# SM3320-BATT-EV.net
KiCad netlist of a schematic drawn in Altium Designer
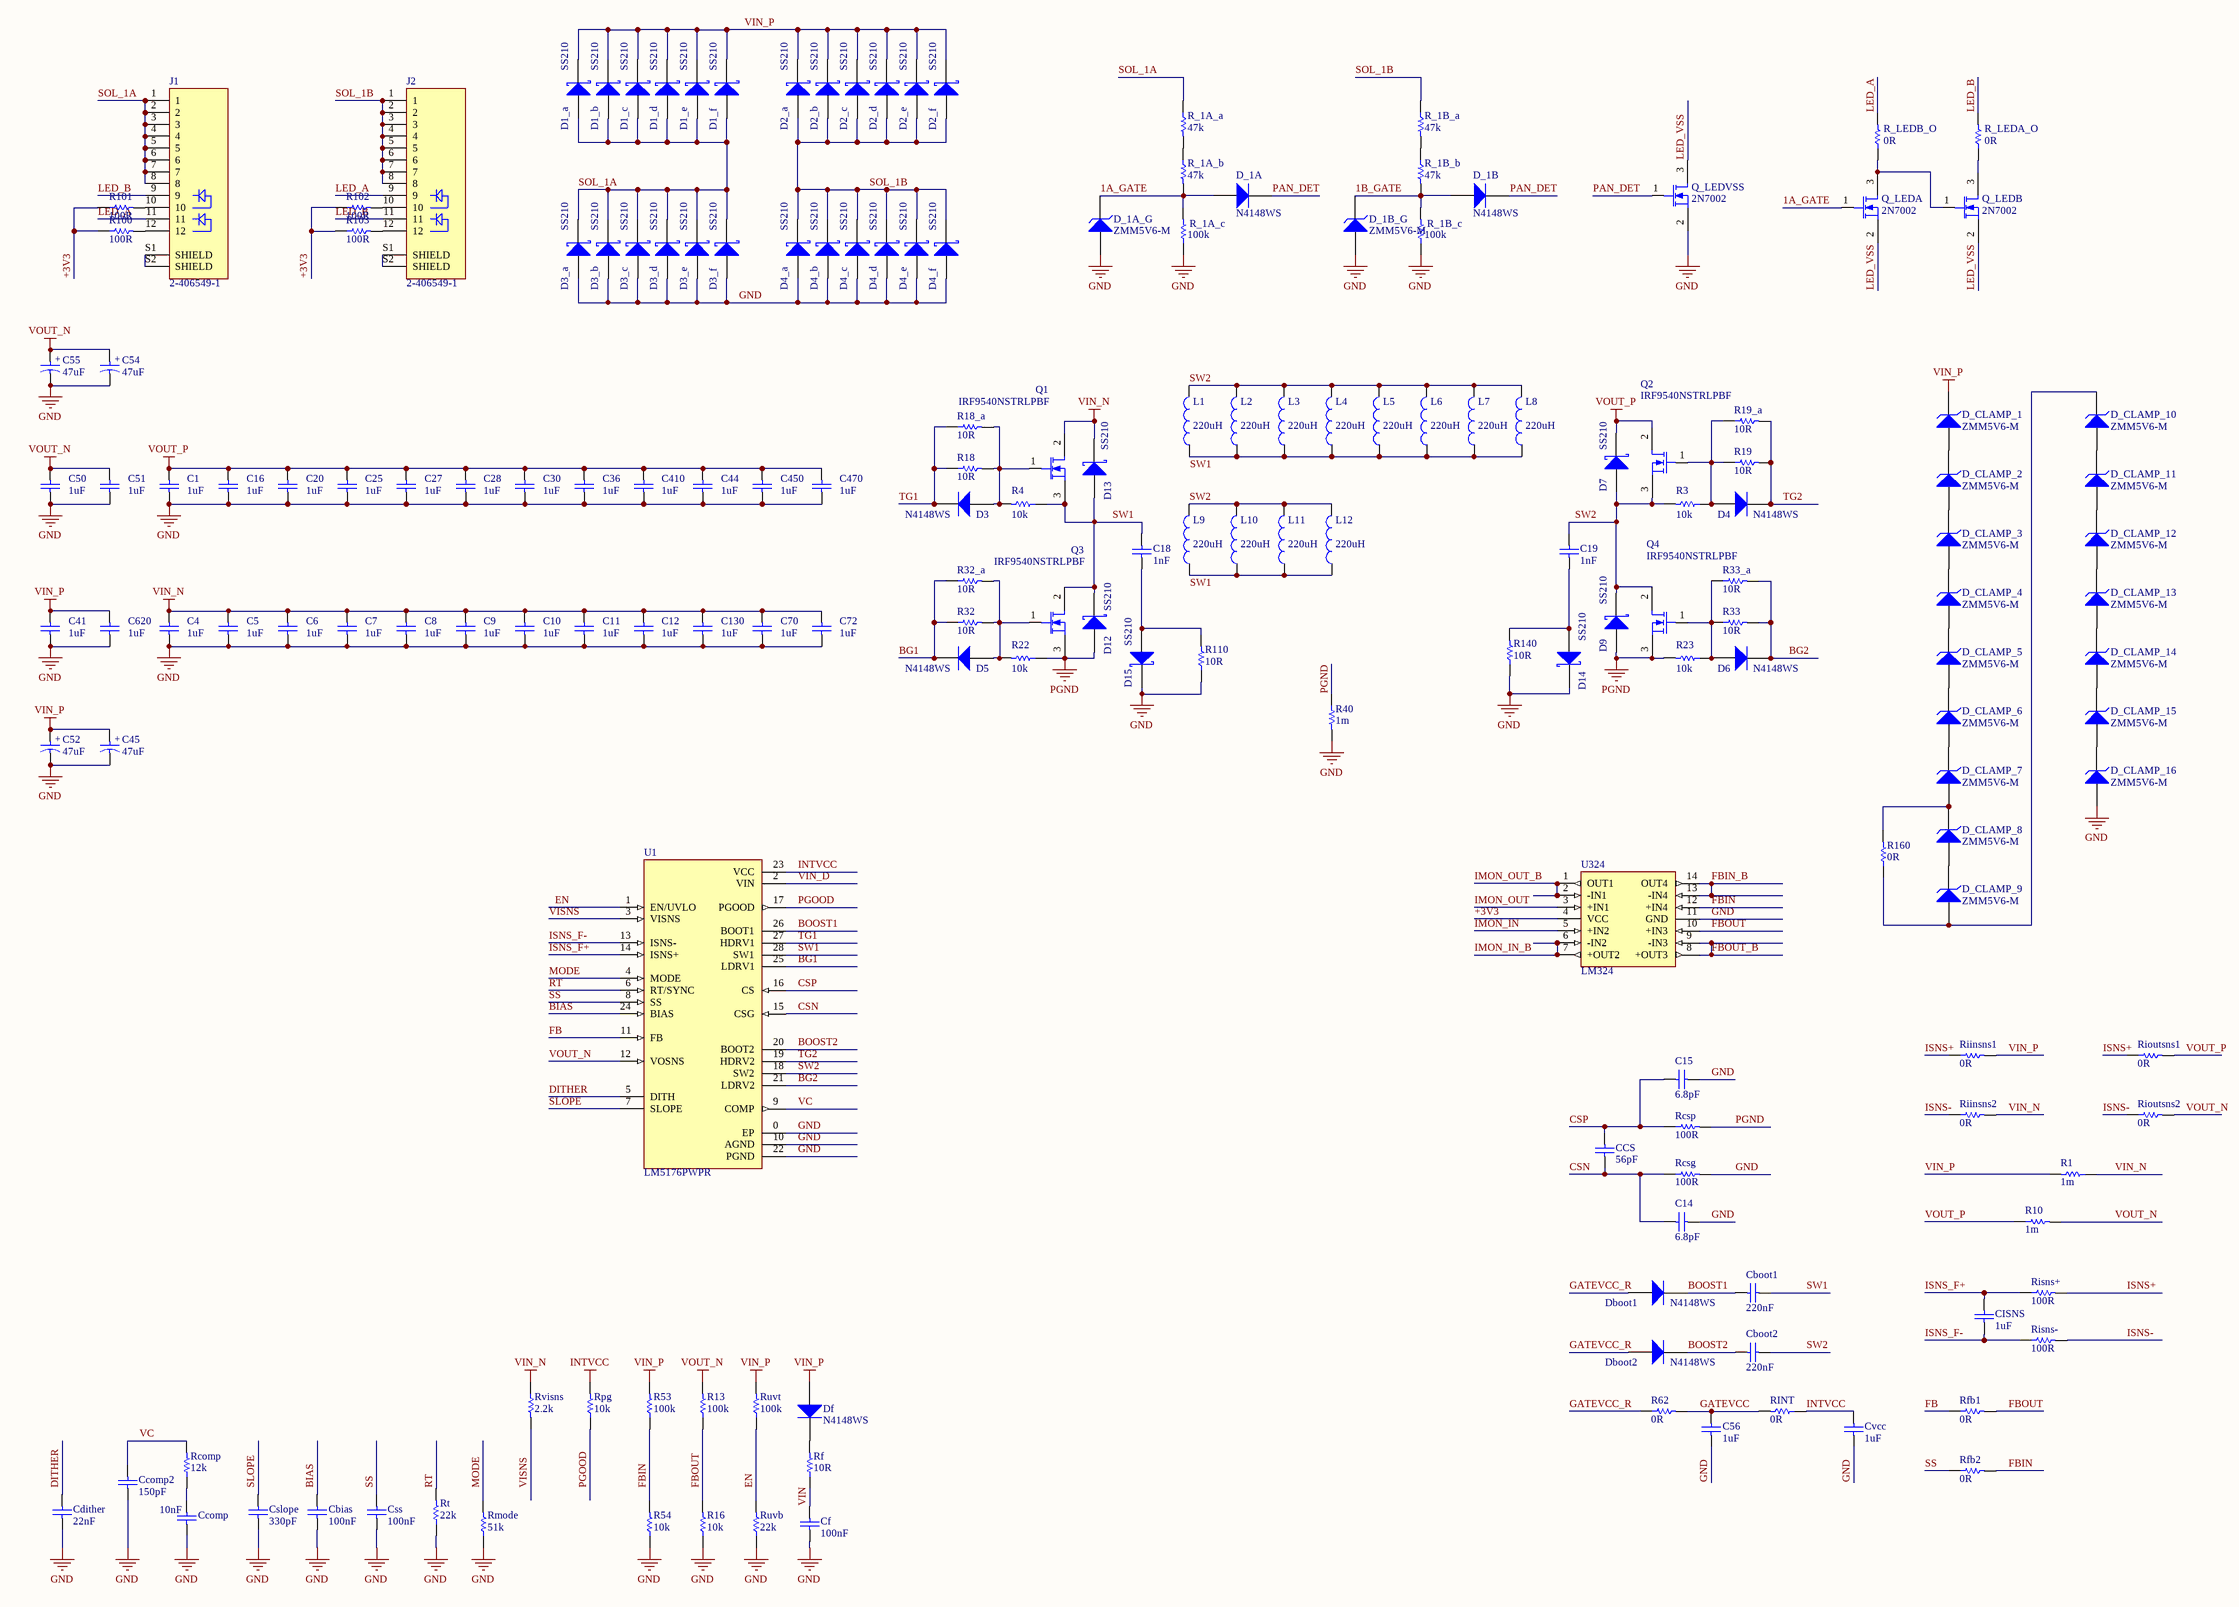
[diagram p0: SM3320-BATT-EV.SchDoc]

(export (version "E")
  (design (tool "Eeschema 10.0.6"))
  (components
    (comp (ref "C1")
      (value "1uF")
      (footprint "C_1206")
      (description "C - CAPACITOR - MLCC - 1uF - 100V - 1206 - X7R")
      (fields (field (name "LCSC PART #") "C91151") (field (name "Comment") "1206B105K101NT"))
      (libsource (lib "JLC_PCB") (part "1206B105K101NT"))
    )
    (comp (ref "C4")
      (value "1uF")
      (footprint "C_1206")
      (description "C - CAPACITOR - MLCC - 1uF - 100V - 1206 - X7R")
      (fields (field (name "LCSC PART #") "C91151") (field (name "Comment") "1206B105K101NT"))
      (libsource (lib "JLC_PCB") (part "1206B105K101NT"))
    )
    (comp (ref "C5")
      (value "1uF")
      (footprint "C_1206")
      (description "C - CAPACITOR - MLCC - 1uF - 100V - 1206 - X7R")
      (fields (field (name "LCSC PART #") "C91151") (field (name "Comment") "1206B105K101NT"))
      (libsource (lib "JLC_PCB") (part "1206B105K101NT"))
    )
    (comp (ref "C6")
      (value "1uF")
      (footprint "C_1206")
      (description "C - CAPACITOR - MLCC - 1uF - 100V - 1206 - X7R")
      (fields (field (name "LCSC PART #") "C91151") (field (name "Comment") "1206B105K101NT"))
      (libsource (lib "JLC_PCB") (part "1206B105K101NT"))
    )
    (comp (ref "C7")
      (value "1uF")
      (footprint "C_1206")
      (description "C - CAPACITOR - MLCC - 1uF - 100V - 1206 - X7R")
      (fields (field (name "LCSC PART #") "C91151") (field (name "Comment") "1206B105K101NT"))
      (libsource (lib "JLC_PCB") (part "1206B105K101NT"))
    )
    (comp (ref "C8")
      (value "1uF")
      (footprint "C_1206")
      (description "C - CAPACITOR - MLCC - 1uF - 100V - 1206 - X7R")
      (fields (field (name "LCSC PART #") "C91151") (field (name "Comment") "1206B105K101NT"))
      (libsource (lib "JLC_PCB") (part "1206B105K101NT"))
    )
    (comp (ref "C9")
      (value "1uF")
      (footprint "C_1206")
      (description "C - CAPACITOR - MLCC - 1uF - 100V - 1206 - X7R")
      (fields (field (name "LCSC PART #") "C91151") (field (name "Comment") "1206B105K101NT"))
      (libsource (lib "JLC_PCB") (part "1206B105K101NT"))
    )
    (comp (ref "C10")
      (value "1uF")
      (footprint "C_1206")
      (description "C - CAPACITOR - MLCC - 1uF - 100V - 1206 - X7R")
      (fields (field (name "LCSC PART #") "C91151") (field (name "Comment") "1206B105K101NT"))
      (libsource (lib "JLC_PCB") (part "1206B105K101NT"))
    )
    (comp (ref "C11")
      (value "1uF")
      (footprint "C_1206")
      (description "C - CAPACITOR - MLCC - 1uF - 100V - 1206 - X7R")
      (fields (field (name "LCSC PART #") "C91151") (field (name "Comment") "1206B105K101NT"))
      (libsource (lib "JLC_PCB") (part "1206B105K101NT"))
    )
    (comp (ref "C12")
      (value "1uF")
      (footprint "C_1206")
      (description "C - CAPACITOR - MLCC - 1uF - 100V - 1206 - X7R")
      (fields (field (name "LCSC PART #") "C91151") (field (name "Comment") "1206B105K101NT"))
      (libsource (lib "JLC_PCB") (part "1206B105K101NT"))
    )
    (comp (ref "C14")
      (value "6.8pF")
      (footprint "C_0402")
      (description "C - CAPACITOR - MLCC - 6.8pF - 50V - 0402")
      (fields (field (name "LCSC PART #") "C1576") (field (name "Comment") "0402CG6R8C500NT"))
      (libsource (lib "JLC_PCB") (part "0402CG6R8C500NT"))
    )
    (comp (ref "C15")
      (value "6.8pF")
      (footprint "C_0402")
      (description "C - CAPACITOR - MLCC - 6.8pF - 50V - 0402")
      (fields (field (name "LCSC PART #") "C1576") (field (name "Comment") "0402CG6R8C500NT"))
      (libsource (lib "JLC_PCB") (part "0402CG6R8C500NT"))
    )
    (comp (ref "C16")
      (value "1uF")
      (footprint "C_1206")
      (description "C - CAPACITOR - MLCC - 1uF - 100V - 1206 - X7R")
      (fields (field (name "LCSC PART #") "C91151") (field (name "Comment") "1206B105K101NT"))
      (libsource (lib "JLC_PCB") (part "1206B105K101NT"))
    )
    (comp (ref "C18")
      (value "1nF")
      (footprint "C_1206")
      (description "C - CAPACITOR - MLCC - 1nF - 2000V - 1206 - X7R")
      (fields (field (name "LCSC PART #") "C9196") (field (name "Comment") "1206B102K202NT"))
      (libsource (lib "JLC_PCB") (part "1206B102K202NT"))
    )
    (comp (ref "C19")
      (value "1nF")
      (footprint "C_1206")
      (description "C - CAPACITOR - MLCC - 1nF - 2000V - 1206 - X7R")
      (fields (field (name "LCSC PART #") "C9196") (field (name "Comment") "1206B102K202NT"))
      (libsource (lib "JLC_PCB") (part "1206B102K202NT"))
    )
    (comp (ref "C20")
      (value "1uF")
      (footprint "C_1206")
      (description "C - CAPACITOR - MLCC - 1uF - 100V - 1206 - X7R")
      (fields (field (name "LCSC PART #") "C91151") (field (name "Comment") "1206B105K101NT"))
      (libsource (lib "JLC_PCB") (part "1206B105K101NT"))
    )
    (comp (ref "C25")
      (value "1uF")
      (footprint "C_1206")
      (description "C - CAPACITOR - MLCC - 1uF - 100V - 1206 - X7R")
      (fields (field (name "LCSC PART #") "C91151") (field (name "Comment") "1206B105K101NT"))
      (libsource (lib "JLC_PCB") (part "1206B105K101NT"))
    )
    (comp (ref "C27")
      (value "1uF")
      (footprint "C_1206")
      (description "C - CAPACITOR - MLCC - 1uF - 100V - 1206 - X7R")
      (fields (field (name "LCSC PART #") "C91151") (field (name "Comment") "1206B105K101NT"))
      (libsource (lib "JLC_PCB") (part "1206B105K101NT"))
    )
    (comp (ref "C28")
      (value "1uF")
      (footprint "C_1206")
      (description "C - CAPACITOR - MLCC - 1uF - 100V - 1206 - X7R")
      (fields (field (name "LCSC PART #") "C91151") (field (name "Comment") "1206B105K101NT"))
      (libsource (lib "JLC_PCB") (part "1206B105K101NT"))
    )
    (comp (ref "C30")
      (value "1uF")
      (footprint "C_1206")
      (description "C - CAPACITOR - MLCC - 1uF - 100V - 1206 - X7R")
      (fields (field (name "LCSC PART #") "C91151") (field (name "Comment") "1206B105K101NT"))
      (libsource (lib "JLC_PCB") (part "1206B105K101NT"))
    )
    (comp (ref "C36")
      (value "1uF")
      (footprint "C_1206")
      (description "C - CAPACITOR - MLCC - 1uF - 100V - 1206 - X7R")
      (fields (field (name "LCSC PART #") "C91151") (field (name "Comment") "1206B105K101NT"))
      (libsource (lib "JLC_PCB") (part "1206B105K101NT"))
    )
    (comp (ref "C41")
      (value "1uF")
      (footprint "C_1206")
      (description "C - CAPACITOR - MLCC - 1uF - 100V - 1206 - X7R")
      (fields (field (name "LCSC PART #") "C91151") (field (name "Comment") "1206B105K101NT"))
      (libsource (lib "JLC_PCB") (part "1206B105K101NT"))
    )
    (comp (ref "C44")
      (value "1uF")
      (footprint "C_1206")
      (description "C - CAPACITOR - MLCC - 1uF - 100V - 1206 - X7R")
      (fields (field (name "LCSC PART #") "C91151") (field (name "Comment") "1206B105K101NT"))
      (libsource (lib "JLC_PCB") (part "1206B105K101NT"))
    )
    (comp (ref "C45")
      (value "47uF")
      (footprint "C_CAN_1010")
      (description "C - CAPACITOR - ELECTROLYTIC - 47uF - 100V")
      (fields (field (name "LCSC PART #") "C164068") (field (name "Comment") "VZH470M2ATR-1010"))
      (libsource (lib "JLC_PCB") (part "VZH470M2ATR-1010"))
    )
    (comp (ref "C50")
      (value "1uF")
      (footprint "C_1206")
      (description "C - CAPACITOR - MLCC - 1uF - 100V - 1206 - X7R")
      (fields (field (name "LCSC PART #") "C91151") (field (name "Comment") "1206B105K101NT"))
      (libsource (lib "JLC_PCB") (part "1206B105K101NT"))
    )
    (comp (ref "C51")
      (value "1uF")
      (footprint "C_1206")
      (description "C - CAPACITOR - MLCC - 1uF - 100V - 1206 - X7R")
      (fields (field (name "LCSC PART #") "C91151") (field (name "Comment") "1206B105K101NT"))
      (libsource (lib "JLC_PCB") (part "1206B105K101NT"))
    )
    (comp (ref "C52")
      (value "47uF")
      (footprint "C_CAN_1010")
      (description "C - CAPACITOR - ELECTROLYTIC - 47uF - 100V")
      (fields (field (name "LCSC PART #") "C164068") (field (name "Comment") "VZH470M2ATR-1010"))
      (libsource (lib "JLC_PCB") (part "VZH470M2ATR-1010"))
    )
    (comp (ref "C54")
      (value "47uF")
      (footprint "C_CAN_1010")
      (description "C - CAPACITOR - ELECTROLYTIC - 47uF - 100V")
      (fields (field (name "LCSC PART #") "C164068") (field (name "Comment") "VZH470M2ATR-1010"))
      (libsource (lib "JLC_PCB") (part "VZH470M2ATR-1010"))
    )
    (comp (ref "C55")
      (value "47uF")
      (footprint "C_CAN_1010")
      (description "C - CAPACITOR - ELECTROLYTIC - 47uF - 100V")
      (fields (field (name "LCSC PART #") "C164068") (field (name "Comment") "VZH470M2ATR-1010"))
      (libsource (lib "JLC_PCB") (part "VZH470M2ATR-1010"))
    )
    (comp (ref "C56")
      (value "1uF")
      (footprint "C_0402")
      (description "C - CAPACITOR - MLCC - 1uF - 25V - 0402")
      (fields (field (name "LCSC PART #") "C52923") (field (name "Comment") "CL05A105KA5NQNC"))
      (libsource (lib "JLC_PCB") (part "CL05A105KA5NQNC"))
    )
    (comp (ref "C70")
      (value "1uF")
      (footprint "C_1206")
      (description "C - CAPACITOR - MLCC - 1uF - 100V - 1206 - X7R")
      (fields (field (name "LCSC PART #") "C91151") (field (name "Comment") "1206B105K101NT"))
      (libsource (lib "JLC_PCB") (part "1206B105K101NT"))
    )
    (comp (ref "C72")
      (value "1uF")
      (footprint "C_1206")
      (description "C - CAPACITOR - MLCC - 1uF - 100V - 1206 - X7R")
      (fields (field (name "LCSC PART #") "C91151") (field (name "Comment") "1206B105K101NT"))
      (libsource (lib "JLC_PCB") (part "1206B105K101NT"))
    )
    (comp (ref "C130")
      (value "1uF")
      (footprint "C_1206")
      (description "C - CAPACITOR - MLCC - 1uF - 100V - 1206 - X7R")
      (fields (field (name "LCSC PART #") "C91151") (field (name "Comment") "1206B105K101NT"))
      (libsource (lib "JLC_PCB") (part "1206B105K101NT"))
    )
    (comp (ref "C410")
      (value "1uF")
      (footprint "C_1206")
      (description "C - CAPACITOR - MLCC - 1uF - 100V - 1206 - X7R")
      (fields (field (name "LCSC PART #") "C91151") (field (name "Comment") "1206B105K101NT"))
      (libsource (lib "JLC_PCB") (part "1206B105K101NT"))
    )
    (comp (ref "C450")
      (value "1uF")
      (footprint "C_1206")
      (description "C - CAPACITOR - MLCC - 1uF - 100V - 1206 - X7R")
      (fields (field (name "LCSC PART #") "C91151") (field (name "Comment") "1206B105K101NT"))
      (libsource (lib "JLC_PCB") (part "1206B105K101NT"))
    )
    (comp (ref "C470")
      (value "1uF")
      (footprint "C_1206")
      (description "C - CAPACITOR - MLCC - 1uF - 100V - 1206 - X7R")
      (fields (field (name "LCSC PART #") "C91151") (field (name "Comment") "1206B105K101NT"))
      (libsource (lib "JLC_PCB") (part "1206B105K101NT"))
    )
    (comp (ref "C620")
      (value "1uF")
      (footprint "C_1206")
      (description "C - CAPACITOR - MLCC - 1uF - 100V - 1206 - X7R")
      (fields (field (name "LCSC PART #") "C91151") (field (name "Comment") "1206B105K101NT"))
      (libsource (lib "JLC_PCB") (part "1206B105K101NT"))
    )
    (comp (ref "Cbias")
      (value "100nF")
      (footprint "C_0603")
      (description "C - CAPACITOR - MLCC - 100nF - 50V - 0603")
      (fields (field (name "LCSC PART #") "C14663") (field (name "Comment") "CC0603KRX7R9BB104"))
      (libsource (lib "JLC_PCB") (part "CC0603KRX7R9BB104"))
    )
    (comp (ref "Cboot1")
      (value "220nF")
      (footprint "C_0402")
      (description "C - CAPACITOR - MLCC - 220nF - 16V - 0402")
      (fields (field (name "LCSC PART #") "C16772") (field (name "Comment") "CL05B224KO5NNNC"))
      (libsource (lib "JLC_PCB") (part "CL05B224KO5NNNC"))
    )
    (comp (ref "Cboot2")
      (value "220nF")
      (footprint "C_0402")
      (description "C - CAPACITOR - MLCC - 220nF - 16V - 0402")
      (fields (field (name "LCSC PART #") "C16772") (field (name "Comment") "CL05B224KO5NNNC"))
      (libsource (lib "JLC_PCB") (part "CL05B224KO5NNNC"))
    )
    (comp (ref "Ccomp")
      (value "10nF")
      (footprint "C_0402")
      (description "C - CAPACITOR - MLCC - 10nF - 50V - 0402")
      (fields (field (name "LCSC PART #") "C15195") (field (name "Comment") "CL05B103KB5NNNC"))
      (libsource (lib "JLC_PCB") (part "CL05B103KB5NNNC"))
    )
    (comp (ref "Ccomp2")
      (value "150pF")
      (footprint "C_0402")
      (description "C - CAPACITOR - MLCC - 150pF - 50V - 0402")
      (fields (field (name "LCSC PART #") "C1527") (field (name "Comment") "0402B151K500NT"))
      (libsource (lib "JLC_PCB") (part "0402B151K500NT"))
    )
    (comp (ref "CCS")
      (value "56pF")
      (footprint "C_0402")
      (description "C - CAPACITOR - MLCC - 56pF - 50V -  0402")
      (fields (field (name "LCSC PART #") "C1572") (field (name "Comment") "0402CG560J500NT"))
      (libsource (lib "JLC_PCB") (part "0402CG560J500NT"))
    )
    (comp (ref "Cdither")
      (value "22nF")
      (footprint "C_0402")
      (description "C - CAPACITOR - MLCC - 22nF - 50V - 0402")
      (fields (field (name "LCSC PART #") "C1532") (field (name "Comment") "0402B223K500NT"))
      (libsource (lib "JLC_PCB") (part "0402B223K500NT"))
    )
    (comp (ref "Cf")
      (value "100nF")
      (footprint "C_0603")
      (description "C - CAPACITOR - MLCC - 100nF - 50V - 0603")
      (fields (field (name "LCSC PART #") "C14663") (field (name "Comment") "CC0603KRX7R9BB104"))
      (libsource (lib "JLC_PCB") (part "CC0603KRX7R9BB104"))
    )
    (comp (ref "CISNS")
      (value "1uF")
      (footprint "C_0402")
      (description "C - CAPACITOR - MLCC - 1uF - 25V - 0402")
      (fields (field (name "LCSC PART #") "C52923") (field (name "Comment") "CL05A105KA5NQNC"))
      (libsource (lib "JLC_PCB") (part "CL05A105KA5NQNC"))
    )
    (comp (ref "Cslope")
      (value "330pF")
      (footprint "C_0603")
      (description "C - CAPACITOR - MLCC - 330pF - 50V - 0603")
      (fields (field (name "LCSC PART #") "C1664") (field (name "Comment") "CL10C331JB8NNNC"))
      (libsource (lib "JLC_PCB") (part "CL10C331JB8NNNC"))
    )
    (comp (ref "Css")
      (value "100nF")
      (footprint "C_0402")
      (description "C - CAPACITOR - MLCC - 100nF - 16V - 0402")
      (fields (field (name "LCSC PART #") "C1525") (field (name "Comment") "CL05B104KO5NNNC"))
      (libsource (lib "JLC_PCB") (part "CL05B104KO5NNNC"))
    )
    (comp (ref "Cvcc")
      (value "1uF")
      (footprint "C_0402")
      (description "C - CAPACITOR - MLCC - 1uF - 25V - 0402")
      (fields (field (name "LCSC PART #") "C52923") (field (name "Comment") "CL05A105KA5NQNC"))
      (libsource (lib "JLC_PCB") (part "CL05A105KA5NQNC"))
    )
    (comp (ref "D1_a")
      (value "SS210")
      (footprint "DO-214AC")
      (description "D - DIODE - SCHOTTKY - 100V - 2A")
      (fields (field (name "LCSC PART #") "C14996"))
      (libsource (lib "JLC_PCB") (part "SS210"))
    )
    (comp (ref "D1_b")
      (value "SS210")
      (footprint "DO-214AC")
      (description "D - DIODE - SCHOTTKY - 100V - 2A")
      (fields (field (name "LCSC PART #") "C14996"))
      (libsource (lib "JLC_PCB") (part "SS210"))
    )
    (comp (ref "D1_c")
      (value "SS210")
      (footprint "DO-214AC")
      (description "D - DIODE - SCHOTTKY - 100V - 2A")
      (fields (field (name "LCSC PART #") "C14996"))
      (libsource (lib "JLC_PCB") (part "SS210"))
    )
    (comp (ref "D1_d")
      (value "SS210")
      (footprint "DO-214AC")
      (description "D - DIODE - SCHOTTKY - 100V - 2A")
      (fields (field (name "LCSC PART #") "C14996"))
      (libsource (lib "JLC_PCB") (part "SS210"))
    )
    (comp (ref "D1_e")
      (value "SS210")
      (footprint "DO-214AC")
      (description "D - DIODE - SCHOTTKY - 100V - 2A")
      (fields (field (name "LCSC PART #") "C14996"))
      (libsource (lib "JLC_PCB") (part "SS210"))
    )
    (comp (ref "D1_f")
      (value "SS210")
      (footprint "DO-214AC")
      (description "D - DIODE - SCHOTTKY - 100V - 2A")
      (fields (field (name "LCSC PART #") "C14996"))
      (libsource (lib "JLC_PCB") (part "SS210"))
    )
    (comp (ref "D2_a")
      (value "SS210")
      (footprint "DO-214AC")
      (description "D - DIODE - SCHOTTKY - 100V - 2A")
      (fields (field (name "LCSC PART #") "C14996"))
      (libsource (lib "JLC_PCB") (part "SS210"))
    )
    (comp (ref "D2_b")
      (value "SS210")
      (footprint "DO-214AC")
      (description "D - DIODE - SCHOTTKY - 100V - 2A")
      (fields (field (name "LCSC PART #") "C14996"))
      (libsource (lib "JLC_PCB") (part "SS210"))
    )
    (comp (ref "D2_c")
      (value "SS210")
      (footprint "DO-214AC")
      (description "D - DIODE - SCHOTTKY - 100V - 2A")
      (fields (field (name "LCSC PART #") "C14996"))
      (libsource (lib "JLC_PCB") (part "SS210"))
    )
    (comp (ref "D2_d")
      (value "SS210")
      (footprint "DO-214AC")
      (description "D - DIODE - SCHOTTKY - 100V - 2A")
      (fields (field (name "LCSC PART #") "C14996"))
      (libsource (lib "JLC_PCB") (part "SS210"))
    )
    (comp (ref "D2_e")
      (value "SS210")
      (footprint "DO-214AC")
      (description "D - DIODE - SCHOTTKY - 100V - 2A")
      (fields (field (name "LCSC PART #") "C14996"))
      (libsource (lib "JLC_PCB") (part "SS210"))
    )
    (comp (ref "D2_f")
      (value "SS210")
      (footprint "DO-214AC")
      (description "D - DIODE - SCHOTTKY - 100V - 2A")
      (fields (field (name "LCSC PART #") "C14996"))
      (libsource (lib "JLC_PCB") (part "SS210"))
    )
    (comp (ref "D3")
      (value "N4148WS")
      (footprint "SOD-323")
      (description "D - DIODE - FAST TRR - 100V - 150mA - 4ns")
      (fields (field (name "LCSC PART #") "C2128"))
      (libsource (lib "JLC_PCB") (part "N4148WS"))
    )
    (comp (ref "D3_a")
      (value "SS210")
      (footprint "DO-214AC")
      (description "D - DIODE - SCHOTTKY - 100V - 2A")
      (fields (field (name "LCSC PART #") "C14996"))
      (libsource (lib "JLC_PCB") (part "SS210"))
    )
    (comp (ref "D3_b")
      (value "SS210")
      (footprint "DO-214AC")
      (description "D - DIODE - SCHOTTKY - 100V - 2A")
      (fields (field (name "LCSC PART #") "C14996"))
      (libsource (lib "JLC_PCB") (part "SS210"))
    )
    (comp (ref "D3_c")
      (value "SS210")
      (footprint "DO-214AC")
      (description "D - DIODE - SCHOTTKY - 100V - 2A")
      (fields (field (name "LCSC PART #") "C14996"))
      (libsource (lib "JLC_PCB") (part "SS210"))
    )
    (comp (ref "D3_d")
      (value "SS210")
      (footprint "DO-214AC")
      (description "D - DIODE - SCHOTTKY - 100V - 2A")
      (fields (field (name "LCSC PART #") "C14996"))
      (libsource (lib "JLC_PCB") (part "SS210"))
    )
    (comp (ref "D3_e")
      (value "SS210")
      (footprint "DO-214AC")
      (description "D - DIODE - SCHOTTKY - 100V - 2A")
      (fields (field (name "LCSC PART #") "C14996"))
      (libsource (lib "JLC_PCB") (part "SS210"))
    )
    (comp (ref "D3_f")
      (value "SS210")
      (footprint "DO-214AC")
      (description "D - DIODE - SCHOTTKY - 100V - 2A")
      (fields (field (name "LCSC PART #") "C14996"))
      (libsource (lib "JLC_PCB") (part "SS210"))
    )
    (comp (ref "D4")
      (value "N4148WS")
      (footprint "SOD-323")
      (description "D - DIODE - FAST TRR - 100V - 150mA - 4ns")
      (fields (field (name "LCSC PART #") "C2128"))
      (libsource (lib "JLC_PCB") (part "N4148WS"))
    )
    (comp (ref "D4_a")
      (value "SS210")
      (footprint "DO-214AC")
      (description "D - DIODE - SCHOTTKY - 100V - 2A")
      (fields (field (name "LCSC PART #") "C14996"))
      (libsource (lib "JLC_PCB") (part "SS210"))
    )
    (comp (ref "D4_b")
      (value "SS210")
      (footprint "DO-214AC")
      (description "D - DIODE - SCHOTTKY - 100V - 2A")
      (fields (field (name "LCSC PART #") "C14996"))
      (libsource (lib "JLC_PCB") (part "SS210"))
    )
    (comp (ref "D4_c")
      (value "SS210")
      (footprint "DO-214AC")
      (description "D - DIODE - SCHOTTKY - 100V - 2A")
      (fields (field (name "LCSC PART #") "C14996"))
      (libsource (lib "JLC_PCB") (part "SS210"))
    )
    (comp (ref "D4_d")
      (value "SS210")
      (footprint "DO-214AC")
      (description "D - DIODE - SCHOTTKY - 100V - 2A")
      (fields (field (name "LCSC PART #") "C14996"))
      (libsource (lib "JLC_PCB") (part "SS210"))
    )
    (comp (ref "D4_e")
      (value "SS210")
      (footprint "DO-214AC")
      (description "D - DIODE - SCHOTTKY - 100V - 2A")
      (fields (field (name "LCSC PART #") "C14996"))
      (libsource (lib "JLC_PCB") (part "SS210"))
    )
    (comp (ref "D4_f")
      (value "SS210")
      (footprint "DO-214AC")
      (description "D - DIODE - SCHOTTKY - 100V - 2A")
      (fields (field (name "LCSC PART #") "C14996"))
      (libsource (lib "JLC_PCB") (part "SS210"))
    )
    (comp (ref "D5")
      (value "N4148WS")
      (footprint "SOD-323")
      (description "D - DIODE - FAST TRR - 100V - 150mA - 4ns")
      (fields (field (name "LCSC PART #") "C2128"))
      (libsource (lib "JLC_PCB") (part "N4148WS"))
    )
    (comp (ref "D6")
      (value "N4148WS")
      (footprint "SOD-323")
      (description "D - DIODE - FAST TRR - 100V - 150mA - 4ns")
      (fields (field (name "LCSC PART #") "C2128"))
      (libsource (lib "JLC_PCB") (part "N4148WS"))
    )
    (comp (ref "D7")
      (value "SS210")
      (footprint "DO-214AC")
      (description "D - DIODE - SCHOTTKY - 100V - 2A")
      (fields (field (name "LCSC PART #") "C14996"))
      (libsource (lib "JLC_PCB") (part "SS210"))
    )
    (comp (ref "D9")
      (value "SS210")
      (footprint "DO-214AC")
      (description "D - DIODE - SCHOTTKY - 100V - 2A")
      (fields (field (name "LCSC PART #") "C14996"))
      (libsource (lib "JLC_PCB") (part "SS210"))
    )
    (comp (ref "D12")
      (value "SS210")
      (footprint "DO-214AC")
      (description "D - DIODE - SCHOTTKY - 100V - 2A")
      (fields (field (name "LCSC PART #") "C14996"))
      (libsource (lib "JLC_PCB") (part "SS210"))
    )
    (comp (ref "D13")
      (value "SS210")
      (footprint "DO-214AC")
      (description "D - DIODE - SCHOTTKY - 100V - 2A")
      (fields (field (name "LCSC PART #") "C14996"))
      (libsource (lib "JLC_PCB") (part "SS210"))
    )
    (comp (ref "D14")
      (value "SS210")
      (footprint "DO-214AC")
      (description "D - DIODE - SCHOTTKY - 100V - 2A")
      (fields (field (name "LCSC PART #") "C14996"))
      (libsource (lib "JLC_PCB") (part "SS210"))
    )
    (comp (ref "D15")
      (value "SS210")
      (footprint "DO-214AC")
      (description "D - DIODE - SCHOTTKY - 100V - 2A")
      (fields (field (name "LCSC PART #") "C14996"))
      (libsource (lib "JLC_PCB") (part "SS210"))
    )
    (comp (ref "Dboot1")
      (value "N4148WS")
      (footprint "SOD-323")
      (description "D - DIODE - FAST TRR - 100V - 150mA - 4ns")
      (fields (field (name "LCSC PART #") "C2128"))
      (libsource (lib "JLC_PCB") (part "N4148WS"))
    )
    (comp (ref "Dboot2")
      (value "N4148WS")
      (footprint "SOD-323")
      (description "D - DIODE - FAST TRR - 100V - 150mA - 4ns")
      (fields (field (name "LCSC PART #") "C2128"))
      (libsource (lib "JLC_PCB") (part "N4148WS"))
    )
    (comp (ref "Df")
      (value "N4148WS")
      (footprint "SOD-323")
      (description "D - DIODE - FAST TRR - 100V - 150mA - 4ns")
      (fields (field (name "LCSC PART #") "C2128"))
      (libsource (lib "JLC_PCB") (part "N4148WS"))
    )
    (comp (ref "D_1A")
      (value "N4148WS")
      (footprint "SOD-323")
      (description "D - DIODE - FAST TRR - 100V - 150mA - 4ns")
      (fields (field (name "LCSC PART #") "C2128"))
      (libsource (lib "JLC_PCB") (part "N4148WS"))
    )
    (comp (ref "D_1A_G")
      (value "ZMM5V6-M")
      (footprint "DO-213AA")
      (description "D - DIODE - ZENER - 5.6V - 500mW")
      (fields (field (name "LCSC PART #") "C8062"))
      (libsource (lib "JLC_PCB") (part "ZMM5V6-M"))
    )
    (comp (ref "D_1B")
      (value "N4148WS")
      (footprint "SOD-323")
      (description "D - DIODE - FAST TRR - 100V - 150mA - 4ns")
      (fields (field (name "LCSC PART #") "C2128"))
      (libsource (lib "JLC_PCB") (part "N4148WS"))
    )
    (comp (ref "D_1B_G")
      (value "ZMM5V6-M")
      (footprint "DO-213AA")
      (description "D - DIODE - ZENER - 5.6V - 500mW")
      (fields (field (name "LCSC PART #") "C8062"))
      (libsource (lib "JLC_PCB") (part "ZMM5V6-M"))
    )
    (comp (ref "D_CLAMP_1")
      (value "ZMM5V6-M")
      (footprint "DO-213AA")
      (description "D - DIODE - ZENER - 5.6V - 500mW")
      (fields (field (name "LCSC PART #") "C8062"))
      (libsource (lib "JLC_PCB") (part "ZMM5V6-M"))
    )
    (comp (ref "D_CLAMP_2")
      (value "ZMM5V6-M")
      (footprint "DO-213AA")
      (description "D - DIODE - ZENER - 5.6V - 500mW")
      (fields (field (name "LCSC PART #") "C8062"))
      (libsource (lib "JLC_PCB") (part "ZMM5V6-M"))
    )
    (comp (ref "D_CLAMP_3")
      (value "ZMM5V6-M")
      (footprint "DO-213AA")
      (description "D - DIODE - ZENER - 5.6V - 500mW")
      (fields (field (name "LCSC PART #") "C8062"))
      (libsource (lib "JLC_PCB") (part "ZMM5V6-M"))
    )
    (comp (ref "D_CLAMP_4")
      (value "ZMM5V6-M")
      (footprint "DO-213AA")
      (description "D - DIODE - ZENER - 5.6V - 500mW")
      (fields (field (name "LCSC PART #") "C8062"))
      (libsource (lib "JLC_PCB") (part "ZMM5V6-M"))
    )
    (comp (ref "D_CLAMP_5")
      (value "ZMM5V6-M")
      (footprint "DO-213AA")
      (description "D - DIODE - ZENER - 5.6V - 500mW")
      (fields (field (name "LCSC PART #") "C8062"))
      (libsource (lib "JLC_PCB") (part "ZMM5V6-M"))
    )
    (comp (ref "D_CLAMP_6")
      (value "ZMM5V6-M")
      (footprint "DO-213AA")
      (description "D - DIODE - ZENER - 5.6V - 500mW")
      (fields (field (name "LCSC PART #") "C8062"))
      (libsource (lib "JLC_PCB") (part "ZMM5V6-M"))
    )
    (comp (ref "D_CLAMP_7")
      (value "ZMM5V6-M")
      (footprint "DO-213AA")
      (description "D - DIODE - ZENER - 5.6V - 500mW")
      (fields (field (name "LCSC PART #") "C8062"))
      (libsource (lib "JLC_PCB") (part "ZMM5V6-M"))
    )
    (comp (ref "D_CLAMP_8")
      (value "ZMM5V6-M")
      (footprint "DO-213AA")
      (description "D - DIODE - ZENER - 5.6V - 500mW")
      (fields (field (name "LCSC PART #") "C8062"))
      (libsource (lib "JLC_PCB") (part "ZMM5V6-M"))
    )
    (comp (ref "D_CLAMP_9")
      (value "ZMM5V6-M")
      (footprint "DO-213AA")
      (description "D - DIODE - ZENER - 5.6V - 500mW")
      (fields (field (name "LCSC PART #") "C8062"))
      (libsource (lib "JLC_PCB") (part "ZMM5V6-M"))
    )
    (comp (ref "D_CLAMP_10")
      (value "ZMM5V6-M")
      (footprint "DO-213AA")
      (description "D - DIODE - ZENER - 5.6V - 500mW")
      (fields (field (name "LCSC PART #") "C8062"))
      (libsource (lib "JLC_PCB") (part "ZMM5V6-M"))
    )
    (comp (ref "D_CLAMP_11")
      (value "ZMM5V6-M")
      (footprint "DO-213AA")
      (description "D - DIODE - ZENER - 5.6V - 500mW")
      (fields (field (name "LCSC PART #") "C8062"))
      (libsource (lib "JLC_PCB") (part "ZMM5V6-M"))
    )
    (comp (ref "D_CLAMP_12")
      (value "ZMM5V6-M")
      (footprint "DO-213AA")
      (description "D - DIODE - ZENER - 5.6V - 500mW")
      (fields (field (name "LCSC PART #") "C8062"))
      (libsource (lib "JLC_PCB") (part "ZMM5V6-M"))
    )
    (comp (ref "D_CLAMP_13")
      (value "ZMM5V6-M")
      (footprint "DO-213AA")
      (description "D - DIODE - ZENER - 5.6V - 500mW")
      (fields (field (name "LCSC PART #") "C8062"))
      (libsource (lib "JLC_PCB") (part "ZMM5V6-M"))
    )
    (comp (ref "D_CLAMP_14")
      (value "ZMM5V6-M")
      (footprint "DO-213AA")
      (description "D - DIODE - ZENER - 5.6V - 500mW")
      (fields (field (name "LCSC PART #") "C8062"))
      (libsource (lib "JLC_PCB") (part "ZMM5V6-M"))
    )
    (comp (ref "D_CLAMP_15")
      (value "ZMM5V6-M")
      (footprint "DO-213AA")
      (description "D - DIODE - ZENER - 5.6V - 500mW")
      (fields (field (name "LCSC PART #") "C8062"))
      (libsource (lib "JLC_PCB") (part "ZMM5V6-M"))
    )
    (comp (ref "D_CLAMP_16")
      (value "ZMM5V6-M")
      (footprint "DO-213AA")
      (description "D - DIODE - ZENER - 5.6V - 500mW")
      (fields (field (name "LCSC PART #") "C8062"))
      (libsource (lib "JLC_PCB") (part "ZMM5V6-M"))
    )
    (comp (ref "J1")
      (value "2-406549-1")
      (footprint "TE_2-406549-1")
      (description "J - JACK - ETHERNET - Right - THT")
      (fields (field (name "LCSC PART #") "C125068"))
      (libsource (lib "JLC_PCB") (part "2-406549-1"))
    )
    (comp (ref "J2")
      (value "2-406549-1")
      (footprint "TE_2-406549-1")
      (description "J - JACK - ETHERNET - Right - THT")
      (fields (field (name "LCSC PART #") "C125068"))
      (libsource (lib "JLC_PCB") (part "2-406549-1"))
    )
    (comp (ref "L1")
      (value "220uH")
      (footprint "SRR1260")
      (description "L - INDUCTOR - 220uH - 1.6A - 12.5mm")
      (fields (field (name "LCSC PART #") "C169380") (field (name "Comment") "SWRB1207S-221MT"))
      (libsource (lib "JLC_PCB") (part "SWRB1207S-221MT"))
    )
    (comp (ref "L2")
      (value "220uH")
      (footprint "SRR1260")
      (description "L - INDUCTOR - 220uH - 1.6A - 12.5mm")
      (fields (field (name "LCSC PART #") "C169380") (field (name "Comment") "SWRB1207S-221MT"))
      (libsource (lib "JLC_PCB") (part "SWRB1207S-221MT"))
    )
    (comp (ref "L3")
      (value "220uH")
      (footprint "SRR1260")
      (description "L - INDUCTOR - 220uH - 1.6A - 12.5mm")
      (fields (field (name "LCSC PART #") "C169380") (field (name "Comment") "SWRB1207S-221MT"))
      (libsource (lib "JLC_PCB") (part "SWRB1207S-221MT"))
    )
    (comp (ref "L4")
      (value "220uH")
      (footprint "SRR1260")
      (description "L - INDUCTOR - 220uH - 1.6A - 12.5mm")
      (fields (field (name "LCSC PART #") "C169380") (field (name "Comment") "SWRB1207S-221MT"))
      (libsource (lib "JLC_PCB") (part "SWRB1207S-221MT"))
    )
    (comp (ref "L5")
      (value "220uH")
      (footprint "SRR1260")
      (description "L - INDUCTOR - 220uH - 1.6A - 12.5mm")
      (fields (field (name "LCSC PART #") "C169380") (field (name "Comment") "SWRB1207S-221MT"))
      (libsource (lib "JLC_PCB") (part "SWRB1207S-221MT"))
    )
    (comp (ref "L6")
      (value "220uH")
      (footprint "SRR1260")
      (description "L - INDUCTOR - 220uH - 1.6A - 12.5mm")
      (fields (field (name "LCSC PART #") "C169380") (field (name "Comment") "SWRB1207S-221MT"))
      (libsource (lib "JLC_PCB") (part "SWRB1207S-221MT"))
    )
    (comp (ref "L7")
      (value "220uH")
      (footprint "SRR1260")
      (description "L - INDUCTOR - 220uH - 1.6A - 12.5mm")
      (fields (field (name "LCSC PART #") "C169380") (field (name "Comment") "SWRB1207S-221MT"))
      (libsource (lib "JLC_PCB") (part "SWRB1207S-221MT"))
    )
    (comp (ref "L8")
      (value "220uH")
      (footprint "SRR1260")
      (description "L - INDUCTOR - 220uH - 1.6A - 12.5mm")
      (fields (field (name "LCSC PART #") "C169380") (field (name "Comment") "SWRB1207S-221MT"))
      (libsource (lib "JLC_PCB") (part "SWRB1207S-221MT"))
    )
    (comp (ref "L9")
      (value "220uH")
      (footprint "SRR1260")
      (description "L - INDUCTOR - 220uH - 1.6A - 12.5mm")
      (fields (field (name "LCSC PART #") "C169380") (field (name "Comment") "SWRB1207S-221MT"))
      (libsource (lib "JLC_PCB") (part "SWRB1207S-221MT"))
    )
    (comp (ref "L10")
      (value "220uH")
      (footprint "SRR1260")
      (description "L - INDUCTOR - 220uH - 1.6A - 12.5mm")
      (fields (field (name "LCSC PART #") "C169380") (field (name "Comment") "SWRB1207S-221MT"))
      (libsource (lib "JLC_PCB") (part "SWRB1207S-221MT"))
    )
    (comp (ref "L11")
      (value "220uH")
      (footprint "SRR1260")
      (description "L - INDUCTOR - 220uH - 1.6A - 12.5mm")
      (fields (field (name "LCSC PART #") "C169380") (field (name "Comment") "SWRB1207S-221MT"))
      (libsource (lib "JLC_PCB") (part "SWRB1207S-221MT"))
    )
    (comp (ref "L12")
      (value "220uH")
      (footprint "SRR1260")
      (description "L - INDUCTOR - 220uH - 1.6A - 12.5mm")
      (fields (field (name "LCSC PART #") "C169380") (field (name "Comment") "SWRB1207S-221MT"))
      (libsource (lib "JLC_PCB") (part "SWRB1207S-221MT"))
    )
    (comp (ref "Q1")
      (value "IRF9540NSTRLPBF")
      (footprint "TO-263-3")
      (description "Q - TRANSISTOR - MOSFET (N) - 250V - 33A - 0.094R")
      (fields (field (name "LCSC PART #") "C33903"))
      (libsource (lib "JLC_PCB") (part "IRF9540NSTRLPBF"))
    )
    (comp (ref "Q2")
      (value "IRF9540NSTRLPBF")
      (footprint "TO-263-3")
      (description "Q - TRANSISTOR - MOSFET (N) - 250V - 33A - 0.094R")
      (fields (field (name "LCSC PART #") "C33903"))
      (libsource (lib "JLC_PCB") (part "IRF9540NSTRLPBF"))
    )
    (comp (ref "Q3")
      (value "IRF9540NSTRLPBF")
      (footprint "TO-263-3")
      (description "Q - TRANSISTOR - MOSFET (N) - 250V - 33A - 0.094R")
      (fields (field (name "LCSC PART #") "C33903"))
      (libsource (lib "JLC_PCB") (part "IRF9540NSTRLPBF"))
    )
    (comp (ref "Q4")
      (value "IRF9540NSTRLPBF")
      (footprint "TO-263-3")
      (description "Q - TRANSISTOR - MOSFET (N) - 250V - 33A - 0.094R")
      (fields (field (name "LCSC PART #") "C33903"))
      (libsource (lib "JLC_PCB") (part "IRF9540NSTRLPBF"))
    )
    (comp (ref "Q_LEDA")
      (value "2N7002")
      (footprint "TO-236AB")
      (description "Q - TRANSISTOR - MOSFET (N) - 60V - 200mW")
      (fields (field (name "LCSC PART #") "C8545"))
      (libsource (lib "JLC_PCB") (part "2N7002"))
    )
    (comp (ref "Q_LEDB")
      (value "2N7002")
      (footprint "TO-236AB")
      (description "Q - TRANSISTOR - MOSFET (N) - 60V - 200mW")
      (fields (field (name "LCSC PART #") "C8545"))
      (libsource (lib "JLC_PCB") (part "2N7002"))
    )
    (comp (ref "Q_LEDVSS")
      (value "2N7002")
      (footprint "TO-236AB")
      (description "Q - TRANSISTOR - MOSFET (N) - 60V - 200mW")
      (fields (field (name "LCSC PART #") "C8545"))
      (libsource (lib "JLC_PCB") (part "2N7002"))
    )
    (comp (ref "R1")
      (value "1m")
      (footprint "R_2512")
      (description "R - RESISTOR - SMD - 0.001R - 1% - 2512 - 2W - 50ppm/k")
      (fields (field (name "LCSC PART #") "C349153") (field (name "POWER") "2W"))
      (libsource (lib "JLC_PCB") (part "EWSL2512F1L00S9"))
    )
    (comp (ref "R3")
      (value "10k")
      (footprint "R_0402")
      (description "R - RESISTOR - SMD - 10k - 1% - 0402")
      (fields (field (name "LCSC PART #") "C25744") (field (name "Comment") "0402WGF1002TCE"))
      (libsource (lib "JLC_PCB") (part "0402WGF1002TCE"))
    )
    (comp (ref "R4")
      (value "10k")
      (footprint "R_0402")
      (description "R - RESISTOR - SMD - 10k - 1% - 0402")
      (fields (field (name "LCSC PART #") "C25744") (field (name "Comment") "0402WGF1002TCE"))
      (libsource (lib "JLC_PCB") (part "0402WGF1002TCE"))
    )
    (comp (ref "R10")
      (value "1m")
      (footprint "R_2512")
      (description "R - RESISTOR - SMD - 0.001R - 1% - 2512 - 2W - 50ppm/k")
      (fields (field (name "LCSC PART #") "C349153") (field (name "POWER") "2W"))
      (libsource (lib "JLC_PCB") (part "EWSL2512F1L00S9"))
    )
    (comp (ref "R13")
      (value "100k")
      (footprint "R_0603")
      (description "R - RESISTOR - SMD - 100k - 1% -  0603")
      (fields (field (name "LCSC PART #") "C22936") (field (name "Comment") "0603WAF100KT5E"))
      (libsource (lib "JLC_PCB") (part "0603WAF100KT5E"))
    )
    (comp (ref "R16")
      (value "10k")
      (footprint "R_0603")
      (description "R - RESISTOR - SMD - 10k - 1% - 0603")
      (fields (field (name "LCSC PART #") "C25804") (field (name "Comment") "0603WAF1002T5E"))
      (libsource (lib "JLC_PCB") (part "0603WAF1002T5E"))
    )
    (comp (ref "R18")
      (value "10R")
      (footprint "R_0402")
      (description "R - RESISTOR - SMD - 10R - 1% - 0402")
      (fields (field (name "LCSC PART #") "C25077") (field (name "Comment") "0402WGF100JTCE"))
      (libsource (lib "JLC_PCB") (part "0402WGF100JTCE"))
    )
    (comp (ref "R18_a")
      (value "10R")
      (footprint "R_0402")
      (description "R - RESISTOR - SMD - 10R - 1% - 0402")
      (fields (field (name "LCSC PART #") "C25077") (field (name "Comment") "0402WGF100JTCE"))
      (libsource (lib "JLC_PCB") (part "0402WGF100JTCE"))
    )
    (comp (ref "R19")
      (value "10R")
      (footprint "R_0402")
      (description "R - RESISTOR - SMD - 10R - 1% - 0402")
      (fields (field (name "LCSC PART #") "C25077") (field (name "Comment") "0402WGF100JTCE"))
      (libsource (lib "JLC_PCB") (part "0402WGF100JTCE"))
    )
    (comp (ref "R19_a")
      (value "10R")
      (footprint "R_0402")
      (description "R - RESISTOR - SMD - 10R - 1% - 0402")
      (fields (field (name "LCSC PART #") "C25077") (field (name "Comment") "0402WGF100JTCE"))
      (libsource (lib "JLC_PCB") (part "0402WGF100JTCE"))
    )
    (comp (ref "R22")
      (value "10k")
      (footprint "R_0402")
      (description "R - RESISTOR - SMD - 10k - 1% - 0402")
      (fields (field (name "LCSC PART #") "C25744") (field (name "Comment") "0402WGF1002TCE"))
      (libsource (lib "JLC_PCB") (part "0402WGF1002TCE"))
    )
    (comp (ref "R23")
      (value "10k")
      (footprint "R_0402")
      (description "R - RESISTOR - SMD - 10k - 1% - 0402")
      (fields (field (name "LCSC PART #") "C25744") (field (name "Comment") "0402WGF1002TCE"))
      (libsource (lib "JLC_PCB") (part "0402WGF1002TCE"))
    )
    (comp (ref "R32")
      (value "10R")
      (footprint "R_0402")
      (description "R - RESISTOR - SMD - 10R - 1% - 0402")
      (fields (field (name "LCSC PART #") "C25077") (field (name "Comment") "0402WGF100JTCE"))
      (libsource (lib "JLC_PCB") (part "0402WGF100JTCE"))
    )
    (comp (ref "R32_a")
      (value "10R")
      (footprint "R_0402")
      (description "R - RESISTOR - SMD - 10R - 1% - 0402")
      (fields (field (name "LCSC PART #") "C25077") (field (name "Comment") "0402WGF100JTCE"))
      (libsource (lib "JLC_PCB") (part "0402WGF100JTCE"))
    )
    (comp (ref "R33")
      (value "10R")
      (footprint "R_0402")
      (description "R - RESISTOR - SMD - 10R - 1% - 0402")
      (fields (field (name "LCSC PART #") "C25077") (field (name "Comment") "0402WGF100JTCE"))
      (libsource (lib "JLC_PCB") (part "0402WGF100JTCE"))
    )
    (comp (ref "R33_a")
      (value "10R")
      (footprint "R_0402")
      (description "R - RESISTOR - SMD - 10R - 1% - 0402")
      (fields (field (name "LCSC PART #") "C25077") (field (name "Comment") "0402WGF100JTCE"))
      (libsource (lib "JLC_PCB") (part "0402WGF100JTCE"))
    )
    (comp (ref "R40")
      (value "1m")
      (footprint "R_2512")
      (description "R - RESISTOR - SMD - 0.001R - 1% - 2512 - 2W - 50ppm/k")
      (fields (field (name "LCSC PART #") "C349153") (field (name "POWER") "2W"))
      (libsource (lib "JLC_PCB") (part "EWSL2512F1L00S9"))
    )
    (comp (ref "R53")
      (value "100k")
      (footprint "R_0603")
      (description "R - RESISTOR - SMD - 100k - 1% -  0603")
      (fields (field (name "LCSC PART #") "C22936") (field (name "Comment") "0603WAF100KT5E"))
      (libsource (lib "JLC_PCB") (part "0603WAF100KT5E"))
    )
    (comp (ref "R54")
      (value "10k")
      (footprint "R_0603")
      (description "R - RESISTOR - SMD - 10k - 1% - 0603")
      (fields (field (name "LCSC PART #") "C25804") (field (name "Comment") "0603WAF1002T5E"))
      (libsource (lib "JLC_PCB") (part "0603WAF1002T5E"))
    )
    (comp (ref "R62")
      (value "0R")
      (footprint "R_0402")
      (description "R - RESISTOR - SMD - 0R - 1% - 0402")
      (fields (field (name "LCSC PART #") "C17168") (field (name "Comment") "0402WGF0000TCE"))
      (libsource (lib "JLC_PCB") (part "0402WGF0000TCE"))
    )
    (comp (ref "R100")
      (value "100R")
      (footprint "R_0402")
      (description "R - RESISTOR - SMD - 100R - 1% - 0402")
      (fields (field (name "LCSC PART #") "C25076") (field (name "Comment") "0402WGF1000TCE"))
      (libsource (lib "JLC_PCB") (part "0402WGF1000TCE"))
    )
    (comp (ref "R101")
      (value "100R")
      (footprint "R_0402")
      (description "R - RESISTOR - SMD - 100R - 1% - 0402")
      (fields (field (name "LCSC PART #") "C25076") (field (name "Comment") "0402WGF1000TCE"))
      (libsource (lib "JLC_PCB") (part "0402WGF1000TCE"))
    )
    (comp (ref "R102")
      (value "100R")
      (footprint "R_0402")
      (description "R - RESISTOR - SMD - 100R - 1% - 0402")
      (fields (field (name "LCSC PART #") "C25076") (field (name "Comment") "0402WGF1000TCE"))
      (libsource (lib "JLC_PCB") (part "0402WGF1000TCE"))
    )
    (comp (ref "R103")
      (value "100R")
      (footprint "R_0402")
      (description "R - RESISTOR - SMD - 100R - 1% - 0402")
      (fields (field (name "LCSC PART #") "C25076") (field (name "Comment") "0402WGF1000TCE"))
      (libsource (lib "JLC_PCB") (part "0402WGF1000TCE"))
    )
    (comp (ref "R110")
      (value "10R")
      (footprint "R_1206")
      (description "R - RESISTOR - SMD - 10R - 1% - 1206")
      (fields (field (name "LCSC PART #") "C17903") (field (name "Comment") "1206W4F100JT5E"))
      (libsource (lib "JLC_PCB") (part "1206W4F100JT5E"))
    )
    (comp (ref "R140")
      (value "10R")
      (footprint "R_1206")
      (description "R - RESISTOR - SMD - 10R - 1% - 1206")
      (fields (field (name "LCSC PART #") "C17903") (field (name "Comment") "1206W4F100JT5E"))
      (libsource (lib "JLC_PCB") (part "1206W4F100JT5E"))
    )
    (comp (ref "R160")
      (value "0R")
      (footprint "R_0402")
      (description "R - RESISTOR - SMD - 0R - 1% - 0402")
      (fields (field (name "LCSC PART #") "C17168") (field (name "Comment") "0402WGF0000TCE"))
      (libsource (lib "JLC_PCB") (part "0402WGF0000TCE"))
    )
    (comp (ref "Rcomp")
      (value "12k")
      (footprint "R_0402")
      (description "R - RESISTOR - SMD - 12k - 1% - 0402")
      (fields (field (name "LCSC PART #") "C25752") (field (name "Comment") "0402WGF1202TCE"))
      (libsource (lib "JLC_PCB") (part "0402WGF1202TCE"))
    )
    (comp (ref "Rcsg")
      (value "100R")
      (footprint "R_0402")
      (description "R - RESISTOR - SMD - 100R - 1% - 0402")
      (fields (field (name "LCSC PART #") "C25076") (field (name "Comment") "0402WGF1000TCE"))
      (libsource (lib "JLC_PCB") (part "0402WGF1000TCE"))
    )
    (comp (ref "Rcsp")
      (value "100R")
      (footprint "R_0402")
      (description "R - RESISTOR - SMD - 100R - 1% - 0402")
      (fields (field (name "LCSC PART #") "C25076") (field (name "Comment") "0402WGF1000TCE"))
      (libsource (lib "JLC_PCB") (part "0402WGF1000TCE"))
    )
    (comp (ref "Rf")
      (value "10R")
      (footprint "R_0402")
      (description "R - RESISTOR - SMD - 10R - 1% - 0402")
      (fields (field (name "LCSC PART #") "C25077") (field (name "Comment") "0402WGF100JTCE"))
      (libsource (lib "JLC_PCB") (part "0402WGF100JTCE"))
    )
    (comp (ref "Rfb1")
      (value "0R")
      (footprint "R_0402")
      (description "R - RESISTOR - SMD - 0R - 1% - 0402")
      (fields (field (name "LCSC PART #") "C17168") (field (name "Comment") "0402WGF0000TCE"))
      (libsource (lib "JLC_PCB") (part "0402WGF0000TCE"))
    )
    (comp (ref "Rfb2")
      (value "0R")
      (footprint "R_0402")
      (description "R - RESISTOR - SMD - 0R - 1% - 0402")
      (fields (field (name "LCSC PART #") "C17168") (field (name "Comment") "0402WGF0000TCE"))
      (libsource (lib "JLC_PCB") (part "0402WGF0000TCE"))
    )
    (comp (ref "Riinsns1")
      (value "0R")
      (footprint "R_0402")
      (description "R - RESISTOR - SMD - 0R - 1% - 0402")
      (fields (field (name "LCSC PART #") "C17168") (field (name "Comment") "0402WGF0000TCE"))
      (libsource (lib "JLC_PCB") (part "0402WGF0000TCE"))
    )
    (comp (ref "Riinsns2")
      (value "0R")
      (footprint "R_0402")
      (description "R - RESISTOR - SMD - 0R - 1% - 0402")
      (fields (field (name "LCSC PART #") "C17168") (field (name "Comment") "0402WGF0000TCE"))
      (libsource (lib "JLC_PCB") (part "0402WGF0000TCE"))
    )
    (comp (ref "RINT")
      (value "0R")
      (footprint "R_0402")
      (description "R - RESISTOR - SMD - 0R - 1% - 0402")
      (fields (field (name "LCSC PART #") "C17168") (field (name "Comment") "0402WGF0000TCE"))
      (libsource (lib "JLC_PCB") (part "0402WGF0000TCE"))
    )
    (comp (ref "Rioutsns1")
      (value "0R")
      (footprint "R_0402")
      (description "R - RESISTOR - SMD - 0R - 1% - 0402")
      (fields (field (name "LCSC PART #") "C17168") (field (name "Comment") "0402WGF0000TCE"))
      (libsource (lib "JLC_PCB") (part "0402WGF0000TCE"))
    )
    (comp (ref "Rioutsns2")
      (value "0R")
      (footprint "R_0402")
      (description "R - RESISTOR - SMD - 0R - 1% - 0402")
      (fields (field (name "LCSC PART #") "C17168") (field (name "Comment") "0402WGF0000TCE"))
      (libsource (lib "JLC_PCB") (part "0402WGF0000TCE"))
    )
    (comp (ref "Risns+")
      (value "100R")
      (footprint "R_0402")
      (description "R - RESISTOR - SMD - 100R - 1% - 0402")
      (fields (field (name "LCSC PART #") "C25076") (field (name "Comment") "0402WGF1000TCE"))
      (libsource (lib "JLC_PCB") (part "0402WGF1000TCE"))
    )
    (comp (ref "Risns-")
      (value "100R")
      (footprint "R_0402")
      (description "R - RESISTOR - SMD - 100R - 1% - 0402")
      (fields (field (name "LCSC PART #") "C25076") (field (name "Comment") "0402WGF1000TCE"))
      (libsource (lib "JLC_PCB") (part "0402WGF1000TCE"))
    )
    (comp (ref "Rmode")
      (value "51k")
      (footprint "R_0402")
      (description "R - RESISTOR - SMD - 51k - 1% - 0402")
      (fields (field (name "LCSC PART #") "C25794") (field (name "Comment") "0402WGF5102TCE"))
      (libsource (lib "JLC_PCB") (part "0402WGF5102TCE"))
    )
    (comp (ref "Rpg")
      (value "10k")
      (footprint "R_0402")
      (description "R - RESISTOR - SMD - 10k - 1% - 0402")
      (fields (field (name "LCSC PART #") "C25744") (field (name "Comment") "0402WGF1002TCE"))
      (libsource (lib "JLC_PCB") (part "0402WGF1002TCE"))
    )
    (comp (ref "Rt")
      (value "22k")
      (footprint "R_0402")
      (description "R - RESISTOR - SMD - 22k - 1% - 0402")
      (fields (field (name "LCSC PART #") "C25768") (field (name "Comment") "0402WGF2202TCE"))
      (libsource (lib "JLC_PCB") (part "0402WGF2202TCE"))
    )
    (comp (ref "Ruvb")
      (value "22k")
      (footprint "R_0402")
      (description "R - RESISTOR - SMD - 22k - 1% - 0402")
      (fields (field (name "LCSC PART #") "C25768") (field (name "Comment") "0402WGF2202TCE"))
      (libsource (lib "JLC_PCB") (part "0402WGF2202TCE"))
    )
    (comp (ref "Ruvt")
      (value "100k")
      (footprint "R_0603")
      (description "R - RESISTOR - SMD - 100k - 1% -  0603")
      (fields (field (name "LCSC PART #") "C22936") (field (name "Comment") "0603WAF100KT5E"))
      (libsource (lib "JLC_PCB") (part "0603WAF100KT5E"))
    )
    (comp (ref "Rvisns")
      (value "2.2k")
      (footprint "R_0402")
      (description "R - RESISTOR - SMD - 2.2k - 1% - 0402")
      (fields (field (name "LCSC PART #") "C25879") (field (name "Comment") "0402WGF2201TCE"))
      (libsource (lib "JLC_PCB") (part "0402WGF2201TCE"))
    )
    (comp (ref "R_1A_a")
      (value "47k")
      (footprint "R_0402")
      (description "R - RESISTOR - SMD - 47k - 1% - 0402")
      (fields (field (name "LCSC PART #") "C25792") (field (name "Comment") "0402WGF4702TCE"))
      (libsource (lib "JLC_PCB") (part "0402WGF4702TCE"))
    )
    (comp (ref "R_1A_b")
      (value "47k")
      (footprint "R_0402")
      (description "R - RESISTOR - SMD - 47k - 1% - 0402")
      (fields (field (name "LCSC PART #") "C25792") (field (name "Comment") "0402WGF4702TCE"))
      (libsource (lib "JLC_PCB") (part "0402WGF4702TCE"))
    )
    (comp (ref "R_1A_c")
      (value "100k")
      (footprint "R_0402")
      (description "R - RESISTOR - SMD - 100k - 1% -  0402")
      (fields (field (name "LCSC PART #") "C25741") (field (name "Comment") "0402WGF1003TCE"))
      (libsource (lib "JLC_PCB") (part "0402WGF1003TCE"))
    )
    (comp (ref "R_1B_a")
      (value "47k")
      (footprint "R_0402")
      (description "R - RESISTOR - SMD - 47k - 1% - 0402")
      (fields (field (name "LCSC PART #") "C25792") (field (name "Comment") "0402WGF4702TCE"))
      (libsource (lib "JLC_PCB") (part "0402WGF4702TCE"))
    )
    (comp (ref "R_1B_b")
      (value "47k")
      (footprint "R_0402")
      (description "R - RESISTOR - SMD - 47k - 1% - 0402")
      (fields (field (name "LCSC PART #") "C25792") (field (name "Comment") "0402WGF4702TCE"))
      (libsource (lib "JLC_PCB") (part "0402WGF4702TCE"))
    )
    (comp (ref "R_1B_c")
      (value "100k")
      (footprint "R_0402")
      (description "R - RESISTOR - SMD - 100k - 1% -  0402")
      (fields (field (name "LCSC PART #") "C25741") (field (name "Comment") "0402WGF1003TCE"))
      (libsource (lib "JLC_PCB") (part "0402WGF1003TCE"))
    )
    (comp (ref "R_LEDA_O")
      (value "0R")
      (footprint "R_0402")
      (description "R - RESISTOR - SMD - 0R - 1% - 0402")
      (fields (field (name "LCSC PART #") "C17168") (field (name "Comment") "0402WGF0000TCE"))
      (libsource (lib "JLC_PCB") (part "0402WGF0000TCE"))
    )
    (comp (ref "R_LEDB_O")
      (value "0R")
      (footprint "R_0402")
      (description "R - RESISTOR - SMD - 0R - 1% - 0402")
      (fields (field (name "LCSC PART #") "C17168") (field (name "Comment") "0402WGF0000TCE"))
      (libsource (lib "JLC_PCB") (part "0402WGF0000TCE"))
    )
    (comp (ref "U1")
      (value "LM5176PWPR")
      (footprint "SILICON:TSSOP-28-EP-P0.65MM-W4.4MM")
      (description "U - IC - 55-V wide VIN synchronous 4-switch buck-boost controller 28-HTSSOP -40 to 125")
      (fields (field (name "LCSC PART #") "C442493") (field (name "MP") "LM5176QPWPR"))
      (libsource (lib "JLC_PCB") (part "LM5176PWPR"))
    )
    (comp (ref "U324")
      (value "LM324")
      (footprint "SILICON:SOIC-14-P1.27-W3.5")
      (description "U - IC - OP AMP (QUAD)")
      (fields (field (name "LCSC PART #") "C71035"))
      (libsource (lib "JLC_PCB") (part "LM324DT"))
    )
  )
  (nets
    (net (code "1") (name "/+3V3") (class "Default")
      (node (ref "R100") (pin "1") (pinfunction "1_1") (pintype "passive"))
      (node (ref "R101") (pin "1") (pinfunction "1_1") (pintype "passive"))
      (node (ref "R102") (pin "1") (pinfunction "1_1") (pintype "passive"))
      (node (ref "R103") (pin "1") (pinfunction "1_1") (pintype "passive"))
      (node (ref "U324") (pin "4") (pinfunction "VCC_4") (pintype "power_in"))
    )
    (net (code "2") (name "/1A_GATE") (class "Default")
      (node (ref "D_1A") (pin "2") (pinfunction "A_2") (pintype "passive"))
      (node (ref "D_1A_G") (pin "1") (pinfunction "K_1") (pintype "passive"))
      (node (ref "Q_LEDA") (pin "1") (pinfunction "G_1") (pintype "passive"))
      (node (ref "R_1A_b") (pin "2") (pinfunction "2_2") (pintype "passive"))
      (node (ref "R_1A_c") (pin "2") (pinfunction "2_2") (pintype "passive"))
    )
    (net (code "3") (name "/1B_GATE") (class "Default")
      (node (ref "D_1B") (pin "2") (pinfunction "A_2") (pintype "passive"))
      (node (ref "D_1B_G") (pin "1") (pinfunction "K_1") (pintype "passive"))
      (node (ref "R_1B_b") (pin "2") (pinfunction "2_2") (pintype "passive"))
      (node (ref "R_1B_c") (pin "2") (pinfunction "2_2") (pintype "passive"))
    )
    (net (code "4") (name "/BG1") (class "Default")
      (node (ref "D5") (pin "1") (pinfunction "K_1") (pintype "passive"))
      (node (ref "R32") (pin "1") (pinfunction "1_1") (pintype "passive"))
      (node (ref "R32_a") (pin "1") (pinfunction "1_1") (pintype "passive"))
      (node (ref "U1") (pin "25") (pinfunction "LDRV1_25") (pintype "passive"))
    )
    (net (code "5") (name "/BG2") (class "Default")
      (node (ref "D6") (pin "1") (pinfunction "K_1") (pintype "passive"))
      (node (ref "R33") (pin "2") (pinfunction "2_2") (pintype "passive"))
      (node (ref "R33_a") (pin "2") (pinfunction "2_2") (pintype "passive"))
      (node (ref "U1") (pin "21") (pinfunction "LDRV2_21") (pintype "passive"))
    )
    (net (code "6") (name "/BIAS") (class "Default")
      (node (ref "Cbias") (pin "2") (pinfunction "2_2") (pintype "passive"))
      (node (ref "U1") (pin "24") (pinfunction "BIAS_24") (pintype "input"))
    )
    (net (code "7") (name "/BOOST1") (class "Default")
      (node (ref "Cboot1") (pin "2") (pinfunction "2_2") (pintype "passive"))
      (node (ref "Dboot1") (pin "1") (pinfunction "K_1") (pintype "passive"))
      (node (ref "U1") (pin "26") (pinfunction "BOOT1_26") (pintype "passive"))
    )
    (net (code "8") (name "/BOOST2") (class "Default")
      (node (ref "Cboot2") (pin "2") (pinfunction "2_2") (pintype "passive"))
      (node (ref "Dboot2") (pin "1") (pinfunction "K_1") (pintype "passive"))
      (node (ref "U1") (pin "20") (pinfunction "BOOT2_20") (pintype "passive"))
    )
    (net (code "9") (name "/CSN") (class "Default")
      (node (ref "C14") (pin "1") (pinfunction "1_1") (pintype "passive"))
      (node (ref "CCS") (pin "1") (pinfunction "1_1") (pintype "passive"))
      (node (ref "Rcsg") (pin "1") (pinfunction "1_1") (pintype "passive"))
      (node (ref "U1") (pin "15") (pinfunction "CSG_15") (pintype "input"))
    )
    (net (code "10") (name "/CSP") (class "Default")
      (node (ref "C15") (pin "1") (pinfunction "1_1") (pintype "passive"))
      (node (ref "CCS") (pin "2") (pinfunction "2_2") (pintype "passive"))
      (node (ref "Rcsp") (pin "1") (pinfunction "1_1") (pintype "passive"))
      (node (ref "U1") (pin "16") (pinfunction "CS_16") (pintype "input"))
    )
    (net (code "11") (name "/DITHER") (class "Default")
      (node (ref "Cdither") (pin "2") (pinfunction "2_2") (pintype "passive"))
      (node (ref "U1") (pin "5") (pinfunction "DITH_5") (pintype "passive"))
    )
    (net (code "12") (name "/EN") (class "Default")
      (node (ref "Ruvb") (pin "2") (pinfunction "2_2") (pintype "passive"))
      (node (ref "Ruvt") (pin "1") (pinfunction "1_1") (pintype "passive"))
      (node (ref "U1") (pin "1") (pinfunction "EN/UVLO_1") (pintype "input"))
    )
    (net (code "13") (name "/FB") (class "Default")
      (node (ref "Rfb1") (pin "1") (pinfunction "1_1") (pintype "passive"))
      (node (ref "U1") (pin "11") (pinfunction "FB_11") (pintype "input"))
    )
    (net (code "14") (name "/FBIN") (class "Default")
      (node (ref "R53") (pin "1") (pinfunction "1_1") (pintype "passive"))
      (node (ref "R54") (pin "2") (pinfunction "2_2") (pintype "passive"))
      (node (ref "Rfb2") (pin "2") (pinfunction "2_2") (pintype "passive"))
      (node (ref "U324") (pin "12") (pinfunction "+IN4_12") (pintype "input"))
    )
    (net (code "15") (name "/FBIN_B") (class "Default")
      (node (ref "U324") (pin "13") (pinfunction "-IN4_13") (pintype "input"))
      (node (ref "U324") (pin "14") (pinfunction "OUT4_14") (pintype "output"))
    )
    (net (code "16") (name "/FBOUT") (class "Default")
      (node (ref "R13") (pin "1") (pinfunction "1_1") (pintype "passive"))
      (node (ref "R16") (pin "2") (pinfunction "2_2") (pintype "passive"))
      (node (ref "Rfb1") (pin "2") (pinfunction "2_2") (pintype "passive"))
      (node (ref "U324") (pin "10") (pinfunction "+IN3_10") (pintype "input"))
    )
    (net (code "17") (name "/FBOUT_B") (class "Default")
      (node (ref "U324") (pin "8") (pinfunction "+OUT3_8") (pintype "output"))
      (node (ref "U324") (pin "9") (pinfunction "-IN3_9") (pintype "input"))
    )
    (net (code "18") (name "/GATEVCC") (class "Default")
      (node (ref "C56") (pin "2") (pinfunction "2_2") (pintype "passive"))
      (node (ref "R62") (pin "2") (pinfunction "2_2") (pintype "passive"))
      (node (ref "RINT") (pin "2") (pinfunction "2_2") (pintype "passive"))
    )
    (net (code "19") (name "/GATEVCC_R") (class "Default")
      (node (ref "Dboot1") (pin "2") (pinfunction "A_2") (pintype "passive"))
      (node (ref "Dboot2") (pin "2") (pinfunction "A_2") (pintype "passive"))
      (node (ref "R62") (pin "1") (pinfunction "1_1") (pintype "passive"))
    )
    (net (code "20") (name "/IMON_IN") (class "Default")
      (node (ref "U324") (pin "5") (pinfunction "+IN2_5") (pintype "input"))
    )
    (net (code "21") (name "/IMON_IN_B") (class "Default")
      (node (ref "U324") (pin "6") (pinfunction "-IN2_6") (pintype "input"))
      (node (ref "U324") (pin "7") (pinfunction "+OUT2_7") (pintype "output"))
    )
    (net (code "22") (name "/IMON_OUT") (class "Default")
      (node (ref "U324") (pin "3") (pinfunction "+IN1_3") (pintype "input"))
    )
    (net (code "23") (name "/IMON_OUT_B") (class "Default")
      (node (ref "U324") (pin "1") (pinfunction "OUT1_1") (pintype "output"))
      (node (ref "U324") (pin "2") (pinfunction "-IN1_2") (pintype "input"))
    )
    (net (code "24") (name "/ISNS+") (class "Default")
      (node (ref "Riinsns1") (pin "1") (pinfunction "1_1") (pintype "passive"))
      (node (ref "Rioutsns1") (pin "1") (pinfunction "1_1") (pintype "passive"))
      (node (ref "Risns+") (pin "2") (pinfunction "2_2") (pintype "passive"))
    )
    (net (code "25") (name "/ISNS-") (class "Default")
      (node (ref "Riinsns2") (pin "1") (pinfunction "1_1") (pintype "passive"))
      (node (ref "Rioutsns2") (pin "1") (pinfunction "1_1") (pintype "passive"))
      (node (ref "Risns-") (pin "2") (pinfunction "2_2") (pintype "passive"))
    )
    (net (code "26") (name "/ISNS_F+") (class "Default")
      (node (ref "CISNS") (pin "2") (pinfunction "2_2") (pintype "passive"))
      (node (ref "Risns+") (pin "1") (pinfunction "1_1") (pintype "passive"))
      (node (ref "U1") (pin "14") (pinfunction "ISNS+_14") (pintype "input"))
    )
    (net (code "27") (name "/ISNS_F-") (class "Default")
      (node (ref "CISNS") (pin "1") (pinfunction "1_1") (pintype "passive"))
      (node (ref "Risns-") (pin "1") (pinfunction "1_1") (pintype "passive"))
      (node (ref "U1") (pin "13") (pinfunction "ISNS-_13") (pintype "input"))
    )
    (net (code "28") (name "/LED_A") (class "Default")
      (node (ref "J1") (pin "11") (pinfunction "11_11") (pintype "passive"))
      (node (ref "J2") (pin "9") (pinfunction "9_9") (pintype "passive"))
      (node (ref "R_LEDB_O") (pin "2") (pinfunction "2_2") (pintype "passive"))
    )
    (net (code "29") (name "/LED_B") (class "Default")
      (node (ref "J1") (pin "9") (pinfunction "9_9") (pintype "passive"))
      (node (ref "J2") (pin "11") (pinfunction "11_11") (pintype "passive"))
      (node (ref "R_LEDA_O") (pin "2") (pinfunction "2_2") (pintype "passive"))
    )
    (net (code "30") (name "/LED_VSS") (class "Default")
      (node (ref "Q_LEDA") (pin "2") (pinfunction "S_2") (pintype "passive"))
      (node (ref "Q_LEDB") (pin "2") (pinfunction "S_2") (pintype "passive"))
      (node (ref "Q_LEDVSS") (pin "3") (pinfunction "D_3") (pintype "passive"))
    )
    (net (code "31") (name "/MODE") (class "Default")
      (node (ref "Rmode") (pin "2") (pinfunction "2_2") (pintype "passive"))
      (node (ref "U1") (pin "4") (pinfunction "MODE_4") (pintype "input"))
    )
    (net (code "32") (name "/PAN_DET") (class "Default")
      (node (ref "D_1A") (pin "1") (pinfunction "K_1") (pintype "passive"))
      (node (ref "D_1B") (pin "1") (pinfunction "K_1") (pintype "passive"))
      (node (ref "Q_LEDVSS") (pin "1") (pinfunction "G_1") (pintype "passive"))
    )
    (net (code "33") (name "/PGOOD") (class "Default")
      (node (ref "Rpg") (pin "1") (pinfunction "1_1") (pintype "passive"))
      (node (ref "U1") (pin "17") (pinfunction "PGOOD_17") (pintype "output"))
    )
    (net (code "34") (name "/RT") (class "Default")
      (node (ref "Rt") (pin "2") (pinfunction "2_2") (pintype "passive"))
      (node (ref "U1") (pin "6") (pinfunction "RT/SYNC_6") (pintype "input"))
    )
    (net (code "35") (name "/SLOPE") (class "Default")
      (node (ref "Cslope") (pin "2") (pinfunction "2_2") (pintype "passive"))
      (node (ref "U1") (pin "7") (pinfunction "SLOPE_7") (pintype "passive"))
    )
    (net (code "36") (name "/SOL_1A") (class "Default")
      (node (ref "D1_a") (pin "2") (pinfunction "A_2") (pintype "passive"))
      (node (ref "D1_b") (pin "2") (pinfunction "A_2") (pintype "passive"))
      (node (ref "D1_c") (pin "2") (pinfunction "A_2") (pintype "passive"))
      (node (ref "D1_d") (pin "2") (pinfunction "A_2") (pintype "passive"))
      (node (ref "D1_e") (pin "2") (pinfunction "A_2") (pintype "passive"))
      (node (ref "D1_f") (pin "2") (pinfunction "A_2") (pintype "passive"))
      (node (ref "D3_a") (pin "1") (pinfunction "K_1") (pintype "passive"))
      (node (ref "D3_b") (pin "1") (pinfunction "K_1") (pintype "passive"))
      (node (ref "D3_c") (pin "1") (pinfunction "K_1") (pintype "passive"))
      (node (ref "D3_d") (pin "1") (pinfunction "K_1") (pintype "passive"))
      (node (ref "D3_e") (pin "1") (pinfunction "K_1") (pintype "passive"))
      (node (ref "D3_f") (pin "1") (pinfunction "K_1") (pintype "passive"))
      (node (ref "J1") (pin "1") (pinfunction "1_1") (pintype "passive"))
      (node (ref "J1") (pin "2") (pinfunction "2_2") (pintype "passive"))
      (node (ref "J1") (pin "3") (pinfunction "3_3") (pintype "passive"))
      (node (ref "J1") (pin "4") (pinfunction "4_4") (pintype "passive"))
      (node (ref "J1") (pin "5") (pinfunction "5_5") (pintype "passive"))
      (node (ref "J1") (pin "6") (pinfunction "6_6") (pintype "passive"))
      (node (ref "J1") (pin "7") (pinfunction "7_7") (pintype "passive"))
      (node (ref "J1") (pin "8") (pinfunction "8_8") (pintype "passive"))
      (node (ref "R_1A_a") (pin "1") (pinfunction "1_1") (pintype "passive"))
    )
    (net (code "37") (name "/SOL_1B") (class "Default")
      (node (ref "D2_a") (pin "2") (pinfunction "A_2") (pintype "passive"))
      (node (ref "D2_b") (pin "2") (pinfunction "A_2") (pintype "passive"))
      (node (ref "D2_c") (pin "2") (pinfunction "A_2") (pintype "passive"))
      (node (ref "D2_d") (pin "2") (pinfunction "A_2") (pintype "passive"))
      (node (ref "D2_e") (pin "2") (pinfunction "A_2") (pintype "passive"))
      (node (ref "D2_f") (pin "2") (pinfunction "A_2") (pintype "passive"))
      (node (ref "D4_a") (pin "1") (pinfunction "K_1") (pintype "passive"))
      (node (ref "D4_b") (pin "1") (pinfunction "K_1") (pintype "passive"))
      (node (ref "D4_c") (pin "1") (pinfunction "K_1") (pintype "passive"))
      (node (ref "D4_d") (pin "1") (pinfunction "K_1") (pintype "passive"))
      (node (ref "D4_e") (pin "1") (pinfunction "K_1") (pintype "passive"))
      (node (ref "D4_f") (pin "1") (pinfunction "K_1") (pintype "passive"))
      (node (ref "J2") (pin "1") (pinfunction "1_1") (pintype "passive"))
      (node (ref "J2") (pin "2") (pinfunction "2_2") (pintype "passive"))
      (node (ref "J2") (pin "3") (pinfunction "3_3") (pintype "passive"))
      (node (ref "J2") (pin "4") (pinfunction "4_4") (pintype "passive"))
      (node (ref "J2") (pin "5") (pinfunction "5_5") (pintype "passive"))
      (node (ref "J2") (pin "6") (pinfunction "6_6") (pintype "passive"))
      (node (ref "J2") (pin "7") (pinfunction "7_7") (pintype "passive"))
      (node (ref "J2") (pin "8") (pinfunction "8_8") (pintype "passive"))
      (node (ref "R_1B_a") (pin "1") (pinfunction "1_1") (pintype "passive"))
    )
    (net (code "38") (name "/SS") (class "Default")
      (node (ref "Css") (pin "2") (pinfunction "2_2") (pintype "passive"))
      (node (ref "Rfb2") (pin "1") (pinfunction "1_1") (pintype "passive"))
      (node (ref "U1") (pin "8") (pinfunction "SS_8") (pintype "input"))
    )
    (net (code "39") (name "/SW1") (class "Default")
      (node (ref "C18") (pin "2") (pinfunction "2_2") (pintype "passive"))
      (node (ref "Cboot1") (pin "1") (pinfunction "1_1") (pintype "passive"))
      (node (ref "D12") (pin "1") (pinfunction "K_1") (pintype "passive"))
      (node (ref "D13") (pin "2") (pinfunction "A_2") (pintype "passive"))
      (node (ref "L1") (pin "1") (pinfunction "1_1") (pintype "passive"))
      (node (ref "L10") (pin "1") (pinfunction "1_1") (pintype "passive"))
      (node (ref "L11") (pin "1") (pinfunction "1_1") (pintype "passive"))
      (node (ref "L12") (pin "1") (pinfunction "1_1") (pintype "passive"))
      (node (ref "L2") (pin "1") (pinfunction "1_1") (pintype "passive"))
      (node (ref "L3") (pin "1") (pinfunction "1_1") (pintype "passive"))
      (node (ref "L4") (pin "1") (pinfunction "1_1") (pintype "passive"))
      (node (ref "L5") (pin "1") (pinfunction "1_1") (pintype "passive"))
      (node (ref "L6") (pin "1") (pinfunction "1_1") (pintype "passive"))
      (node (ref "L7") (pin "1") (pinfunction "1_1") (pintype "passive"))
      (node (ref "L8") (pin "1") (pinfunction "1_1") (pintype "passive"))
      (node (ref "L9") (pin "1") (pinfunction "1_1") (pintype "passive"))
      (node (ref "Q1") (pin "3") (pinfunction "S_3") (pintype "passive"))
      (node (ref "Q3") (pin "2") (pinfunction "D_2") (pintype "passive"))
      (node (ref "R4") (pin "1") (pinfunction "1_1") (pintype "passive"))
      (node (ref "U1") (pin "28") (pinfunction "SW1_28") (pintype "passive"))
    )
    (net (code "40") (name "/SW2") (class "Default")
      (node (ref "C19") (pin "2") (pinfunction "2_2") (pintype "passive"))
      (node (ref "Cboot2") (pin "1") (pinfunction "1_1") (pintype "passive"))
      (node (ref "D7") (pin "2") (pinfunction "A_2") (pintype "passive"))
      (node (ref "D9") (pin "1") (pinfunction "K_1") (pintype "passive"))
      (node (ref "L1") (pin "2") (pinfunction "2_2") (pintype "passive"))
      (node (ref "L10") (pin "2") (pinfunction "2_2") (pintype "passive"))
      (node (ref "L11") (pin "2") (pinfunction "2_2") (pintype "passive"))
      (node (ref "L12") (pin "2") (pinfunction "2_2") (pintype "passive"))
      (node (ref "L2") (pin "2") (pinfunction "2_2") (pintype "passive"))
      (node (ref "L3") (pin "2") (pinfunction "2_2") (pintype "passive"))
      (node (ref "L4") (pin "2") (pinfunction "2_2") (pintype "passive"))
      (node (ref "L5") (pin "2") (pinfunction "2_2") (pintype "passive"))
      (node (ref "L6") (pin "2") (pinfunction "2_2") (pintype "passive"))
      (node (ref "L7") (pin "2") (pinfunction "2_2") (pintype "passive"))
      (node (ref "L8") (pin "2") (pinfunction "2_2") (pintype "passive"))
      (node (ref "L9") (pin "2") (pinfunction "2_2") (pintype "passive"))
      (node (ref "Q2") (pin "3") (pinfunction "S_3") (pintype "passive"))
      (node (ref "Q4") (pin "2") (pinfunction "D_2") (pintype "passive"))
      (node (ref "R3") (pin "2") (pinfunction "2_2") (pintype "passive"))
      (node (ref "U1") (pin "18") (pinfunction "SW2_18") (pintype "passive"))
    )
    (net (code "41") (name "/TG1") (class "Default")
      (node (ref "D3") (pin "1") (pinfunction "K_1") (pintype "passive"))
      (node (ref "R18") (pin "1") (pinfunction "1_1") (pintype "passive"))
      (node (ref "R18_a") (pin "1") (pinfunction "1_1") (pintype "passive"))
      (node (ref "U1") (pin "27") (pinfunction "HDRV1_27") (pintype "passive"))
    )
    (net (code "42") (name "/TG2") (class "Default")
      (node (ref "D4") (pin "1") (pinfunction "K_1") (pintype "passive"))
      (node (ref "R19") (pin "2") (pinfunction "2_2") (pintype "passive"))
      (node (ref "R19_a") (pin "2") (pinfunction "2_2") (pintype "passive"))
      (node (ref "U1") (pin "19") (pinfunction "HDRV2_19") (pintype "passive"))
    )
    (net (code "43") (name "/VC") (class "Default")
      (node (ref "Ccomp2") (pin "2") (pinfunction "2_2") (pintype "passive"))
      (node (ref "Rcomp") (pin "2") (pinfunction "2_2") (pintype "passive"))
      (node (ref "U1") (pin "9") (pinfunction "COMP_9") (pintype "output"))
    )
    (net (code "44") (name "/VIN") (class "Default")
      (node (ref "Cf") (pin "2") (pinfunction "2_2") (pintype "passive"))
      (node (ref "Rf") (pin "1") (pinfunction "1_1") (pintype "passive"))
    )
    (net (code "45") (name "/VIN_D") (class "Default")
      (node (ref "U1") (pin "2") (pinfunction "VIN_2") (pintype "power_in"))
    )
    (net (code "46") (name "/VISNS") (class "Default")
      (node (ref "Rvisns") (pin "2") (pinfunction "2_2") (pintype "passive"))
      (node (ref "U1") (pin "3") (pinfunction "VISNS_3") (pintype "input"))
    )
    (net (code "47") (name "GND") (class "Default")
      (node (ref "C1") (pin "1") (pinfunction "1_1") (pintype "passive"))
      (node (ref "C10") (pin "1") (pinfunction "1_1") (pintype "passive"))
      (node (ref "C11") (pin "1") (pinfunction "1_1") (pintype "passive"))
      (node (ref "C12") (pin "1") (pinfunction "1_1") (pintype "passive"))
      (node (ref "C130") (pin "1") (pinfunction "1_1") (pintype "passive"))
      (node (ref "C14") (pin "2") (pinfunction "2_2") (pintype "passive"))
      (node (ref "C15") (pin "2") (pinfunction "2_2") (pintype "passive"))
      (node (ref "C16") (pin "1") (pinfunction "1_1") (pintype "passive"))
      (node (ref "C20") (pin "1") (pinfunction "1_1") (pintype "passive"))
      (node (ref "C25") (pin "1") (pinfunction "1_1") (pintype "passive"))
      (node (ref "C27") (pin "1") (pinfunction "1_1") (pintype "passive"))
      (node (ref "C28") (pin "1") (pinfunction "1_1") (pintype "passive"))
      (node (ref "C30") (pin "1") (pinfunction "1_1") (pintype "passive"))
      (node (ref "C36") (pin "1") (pinfunction "1_1") (pintype "passive"))
      (node (ref "C4") (pin "1") (pinfunction "1_1") (pintype "passive"))
      (node (ref "C41") (pin "1") (pinfunction "1_1") (pintype "passive"))
      (node (ref "C410") (pin "1") (pinfunction "1_1") (pintype "passive"))
      (node (ref "C44") (pin "1") (pinfunction "1_1") (pintype "passive"))
      (node (ref "C45") (pin "1") (pinfunction "1_1") (pintype "passive"))
      (node (ref "C450") (pin "1") (pinfunction "1_1") (pintype "passive"))
      (node (ref "C470") (pin "1") (pinfunction "1_1") (pintype "passive"))
      (node (ref "C5") (pin "1") (pinfunction "1_1") (pintype "passive"))
      (node (ref "C50") (pin "1") (pinfunction "1_1") (pintype "passive"))
      (node (ref "C51") (pin "1") (pinfunction "1_1") (pintype "passive"))
      (node (ref "C52") (pin "1") (pinfunction "1_1") (pintype "passive"))
      (node (ref "C54") (pin "1") (pinfunction "1_1") (pintype "passive"))
      (node (ref "C55") (pin "1") (pinfunction "1_1") (pintype "passive"))
      (node (ref "C56") (pin "1") (pinfunction "1_1") (pintype "passive"))
      (node (ref "C6") (pin "1") (pinfunction "1_1") (pintype "passive"))
      (node (ref "C620") (pin "1") (pinfunction "1_1") (pintype "passive"))
      (node (ref "C7") (pin "1") (pinfunction "1_1") (pintype "passive"))
      (node (ref "C70") (pin "1") (pinfunction "1_1") (pintype "passive"))
      (node (ref "C72") (pin "1") (pinfunction "1_1") (pintype "passive"))
      (node (ref "C8") (pin "1") (pinfunction "1_1") (pintype "passive"))
      (node (ref "C9") (pin "1") (pinfunction "1_1") (pintype "passive"))
      (node (ref "Cbias") (pin "1") (pinfunction "1_1") (pintype "passive"))
      (node (ref "Ccomp") (pin "1") (pinfunction "1_1") (pintype "passive"))
      (node (ref "Ccomp2") (pin "1") (pinfunction "1_1") (pintype "passive"))
      (node (ref "Cdither") (pin "1") (pinfunction "1_1") (pintype "passive"))
      (node (ref "Cf") (pin "1") (pinfunction "1_1") (pintype "passive"))
      (node (ref "Cslope") (pin "1") (pinfunction "1_1") (pintype "passive"))
      (node (ref "Css") (pin "1") (pinfunction "1_1") (pintype "passive"))
      (node (ref "Cvcc") (pin "1") (pinfunction "1_1") (pintype "passive"))
      (node (ref "D14") (pin "1") (pinfunction "K_1") (pintype "passive"))
      (node (ref "D15") (pin "1") (pinfunction "K_1") (pintype "passive"))
      (node (ref "D3_a") (pin "2") (pinfunction "A_2") (pintype "passive"))
      (node (ref "D3_b") (pin "2") (pinfunction "A_2") (pintype "passive"))
      (node (ref "D3_c") (pin "2") (pinfunction "A_2") (pintype "passive"))
      (node (ref "D3_d") (pin "2") (pinfunction "A_2") (pintype "passive"))
      (node (ref "D3_e") (pin "2") (pinfunction "A_2") (pintype "passive"))
      (node (ref "D3_f") (pin "2") (pinfunction "A_2") (pintype "passive"))
      (node (ref "D4_a") (pin "2") (pinfunction "A_2") (pintype "passive"))
      (node (ref "D4_b") (pin "2") (pinfunction "A_2") (pintype "passive"))
      (node (ref "D4_c") (pin "2") (pinfunction "A_2") (pintype "passive"))
      (node (ref "D4_d") (pin "2") (pinfunction "A_2") (pintype "passive"))
      (node (ref "D4_e") (pin "2") (pinfunction "A_2") (pintype "passive"))
      (node (ref "D4_f") (pin "2") (pinfunction "A_2") (pintype "passive"))
      (node (ref "D_1A_G") (pin "2") (pinfunction "A_2") (pintype "passive"))
      (node (ref "D_1B_G") (pin "2") (pinfunction "A_2") (pintype "passive"))
      (node (ref "D_CLAMP_16") (pin "2") (pinfunction "A_2") (pintype "passive"))
      (node (ref "Q_LEDVSS") (pin "2") (pinfunction "S_2") (pintype "passive"))
      (node (ref "R110") (pin "1") (pinfunction "1_1") (pintype "passive"))
      (node (ref "R140") (pin "1") (pinfunction "1_1") (pintype "passive"))
      (node (ref "R16") (pin "1") (pinfunction "1_1") (pintype "passive"))
      (node (ref "R40") (pin "2") (pinfunction "2_2") (pintype "passive"))
      (node (ref "R54") (pin "1") (pinfunction "1_1") (pintype "passive"))
      (node (ref "R_1A_c") (pin "1") (pinfunction "1_1") (pintype "passive"))
      (node (ref "R_1B_c") (pin "1") (pinfunction "1_1") (pintype "passive"))
      (node (ref "Rcsg") (pin "2") (pinfunction "2_2") (pintype "passive"))
      (node (ref "Rmode") (pin "1") (pinfunction "1_1") (pintype "passive"))
      (node (ref "Rt") (pin "1") (pinfunction "1_1") (pintype "passive"))
      (node (ref "Ruvb") (pin "1") (pinfunction "1_1") (pintype "passive"))
      (node (ref "U1") (pin "0") (pinfunction "EP_0") (pintype "power_in"))
      (node (ref "U1") (pin "10") (pinfunction "AGND_10") (pintype "power_in"))
      (node (ref "U1") (pin "22") (pinfunction "PGND_22") (pintype "power_in"))
      (node (ref "U324") (pin "11") (pinfunction "GND_11") (pintype "power_in"))
    )
    (net (code "48") (name "INTVCC") (class "Default")
      (node (ref "Cvcc") (pin "2") (pinfunction "2_2") (pintype "passive"))
      (node (ref "RINT") (pin "1") (pinfunction "1_1") (pintype "passive"))
      (node (ref "Rpg") (pin "2") (pinfunction "2_2") (pintype "passive"))
      (node (ref "U1") (pin "23") (pinfunction "VCC_23") (pintype "power_in"))
    )
    (net (code "49") (name "Net-(Ccomp-Pad2)") (class "Default")
      (node (ref "Ccomp") (pin "2") (pinfunction "2_2") (pintype "passive"))
      (node (ref "Rcomp") (pin "1") (pinfunction "1_1") (pintype "passive"))
    )
    (net (code "50") (name "Net-(D3-A)") (class "Default")
      (node (ref "D3") (pin "2") (pinfunction "A_2") (pintype "passive"))
      (node (ref "Q1") (pin "1") (pinfunction "G_1") (pintype "passive"))
      (node (ref "R18") (pin "2") (pinfunction "2_2") (pintype "passive"))
      (node (ref "R18_a") (pin "2") (pinfunction "2_2") (pintype "passive"))
      (node (ref "R4") (pin "2") (pinfunction "2_2") (pintype "passive"))
    )
    (net (code "51") (name "Net-(D4-A)") (class "Default")
      (node (ref "D4") (pin "2") (pinfunction "A_2") (pintype "passive"))
      (node (ref "Q2") (pin "1") (pinfunction "G_1") (pintype "passive"))
      (node (ref "R19") (pin "1") (pinfunction "1_1") (pintype "passive"))
      (node (ref "R19_a") (pin "1") (pinfunction "1_1") (pintype "passive"))
      (node (ref "R3") (pin "1") (pinfunction "1_1") (pintype "passive"))
    )
    (net (code "52") (name "Net-(D5-A)") (class "Default")
      (node (ref "D5") (pin "2") (pinfunction "A_2") (pintype "passive"))
      (node (ref "Q3") (pin "1") (pinfunction "G_1") (pintype "passive"))
      (node (ref "R22") (pin "2") (pinfunction "2_2") (pintype "passive"))
      (node (ref "R32") (pin "2") (pinfunction "2_2") (pintype "passive"))
      (node (ref "R32_a") (pin "2") (pinfunction "2_2") (pintype "passive"))
    )
    (net (code "53") (name "Net-(D6-A)") (class "Default")
      (node (ref "D6") (pin "2") (pinfunction "A_2") (pintype "passive"))
      (node (ref "Q4") (pin "1") (pinfunction "G_1") (pintype "passive"))
      (node (ref "R23") (pin "1") (pinfunction "1_1") (pintype "passive"))
      (node (ref "R33") (pin "1") (pinfunction "1_1") (pintype "passive"))
      (node (ref "R33_a") (pin "1") (pinfunction "1_1") (pintype "passive"))
    )
    (net (code "54") (name "Net-(D14-A)") (class "Default")
      (node (ref "C19") (pin "1") (pinfunction "1_1") (pintype "passive"))
      (node (ref "D14") (pin "2") (pinfunction "A_2") (pintype "passive"))
      (node (ref "R140") (pin "2") (pinfunction "2_2") (pintype "passive"))
    )
    (net (code "55") (name "Net-(D15-A)") (class "Default")
      (node (ref "C18") (pin "1") (pinfunction "1_1") (pintype "passive"))
      (node (ref "D15") (pin "2") (pinfunction "A_2") (pintype "passive"))
      (node (ref "R110") (pin "2") (pinfunction "2_2") (pintype "passive"))
    )
    (net (code "56") (name "Net-(D_CLAMP_1-A)") (class "Default")
      (node (ref "D_CLAMP_1") (pin "2") (pinfunction "A_2") (pintype "passive"))
      (node (ref "D_CLAMP_2") (pin "1") (pinfunction "K_1") (pintype "passive"))
    )
    (net (code "57") (name "Net-(D_CLAMP_2-A)") (class "Default")
      (node (ref "D_CLAMP_2") (pin "2") (pinfunction "A_2") (pintype "passive"))
      (node (ref "D_CLAMP_3") (pin "1") (pinfunction "K_1") (pintype "passive"))
    )
    (net (code "58") (name "Net-(D_CLAMP_3-A)") (class "Default")
      (node (ref "D_CLAMP_3") (pin "2") (pinfunction "A_2") (pintype "passive"))
      (node (ref "D_CLAMP_4") (pin "1") (pinfunction "K_1") (pintype "passive"))
    )
    (net (code "59") (name "Net-(D_CLAMP_4-A)") (class "Default")
      (node (ref "D_CLAMP_4") (pin "2") (pinfunction "A_2") (pintype "passive"))
      (node (ref "D_CLAMP_5") (pin "1") (pinfunction "K_1") (pintype "passive"))
    )
    (net (code "60") (name "Net-(D_CLAMP_5-A)") (class "Default")
      (node (ref "D_CLAMP_5") (pin "2") (pinfunction "A_2") (pintype "passive"))
      (node (ref "D_CLAMP_6") (pin "1") (pinfunction "K_1") (pintype "passive"))
    )
    (net (code "61") (name "Net-(D_CLAMP_6-A)") (class "Default")
      (node (ref "D_CLAMP_6") (pin "2") (pinfunction "A_2") (pintype "passive"))
      (node (ref "D_CLAMP_7") (pin "1") (pinfunction "K_1") (pintype "passive"))
    )
    (net (code "62") (name "Net-(D_CLAMP_7-A)") (class "Default")
      (node (ref "D_CLAMP_7") (pin "2") (pinfunction "A_2") (pintype "passive"))
      (node (ref "D_CLAMP_8") (pin "1") (pinfunction "K_1") (pintype "passive"))
      (node (ref "R160") (pin "2") (pinfunction "2_2") (pintype "passive"))
    )
    (net (code "63") (name "Net-(D_CLAMP_8-A)") (class "Default")
      (node (ref "D_CLAMP_8") (pin "2") (pinfunction "A_2") (pintype "passive"))
      (node (ref "D_CLAMP_9") (pin "1") (pinfunction "K_1") (pintype "passive"))
    )
    (net (code "64") (name "Net-(D_CLAMP_10-A)") (class "Default")
      (node (ref "D_CLAMP_10") (pin "2") (pinfunction "A_2") (pintype "passive"))
      (node (ref "D_CLAMP_11") (pin "1") (pinfunction "K_1") (pintype "passive"))
    )
    (net (code "65") (name "Net-(D_CLAMP_10-K)") (class "Default")
      (node (ref "D_CLAMP_10") (pin "1") (pinfunction "K_1") (pintype "passive"))
      (node (ref "D_CLAMP_9") (pin "2") (pinfunction "A_2") (pintype "passive"))
      (node (ref "R160") (pin "1") (pinfunction "1_1") (pintype "passive"))
    )
    (net (code "66") (name "Net-(D_CLAMP_11-A)") (class "Default")
      (node (ref "D_CLAMP_11") (pin "2") (pinfunction "A_2") (pintype "passive"))
      (node (ref "D_CLAMP_12") (pin "1") (pinfunction "K_1") (pintype "passive"))
    )
    (net (code "67") (name "Net-(D_CLAMP_12-A)") (class "Default")
      (node (ref "D_CLAMP_12") (pin "2") (pinfunction "A_2") (pintype "passive"))
      (node (ref "D_CLAMP_13") (pin "1") (pinfunction "K_1") (pintype "passive"))
    )
    (net (code "68") (name "Net-(D_CLAMP_13-A)") (class "Default")
      (node (ref "D_CLAMP_13") (pin "2") (pinfunction "A_2") (pintype "passive"))
      (node (ref "D_CLAMP_14") (pin "1") (pinfunction "K_1") (pintype "passive"))
    )
    (net (code "69") (name "Net-(D_CLAMP_14-A)") (class "Default")
      (node (ref "D_CLAMP_14") (pin "2") (pinfunction "A_2") (pintype "passive"))
      (node (ref "D_CLAMP_15") (pin "1") (pinfunction "K_1") (pintype "passive"))
    )
    (net (code "70") (name "Net-(D_CLAMP_15-A)") (class "Default")
      (node (ref "D_CLAMP_15") (pin "2") (pinfunction "A_2") (pintype "passive"))
      (node (ref "D_CLAMP_16") (pin "1") (pinfunction "K_1") (pintype "passive"))
    )
    (net (code "71") (name "Net-(Df-K)") (class "Default")
      (node (ref "Df") (pin "1") (pinfunction "K_1") (pintype "passive"))
      (node (ref "Rf") (pin "2") (pinfunction "2_2") (pintype "passive"))
    )
    (net (code "72") (name "Net-(J1-Pad10)") (class "Default")
      (node (ref "J1") (pin "10") (pinfunction "10_10") (pintype "passive"))
      (node (ref "R101") (pin "2") (pinfunction "2_2") (pintype "passive"))
    )
    (net (code "73") (name "Net-(J1-Pad12)") (class "Default")
      (node (ref "J1") (pin "12") (pinfunction "12_12") (pintype "passive"))
      (node (ref "R100") (pin "2") (pinfunction "2_2") (pintype "passive"))
    )
    (net (code "74") (name "Net-(J1-SHIELD-PadS1)") (class "Default")
      (node (ref "J1") (pin "S1") (pinfunction "SHIELD_S1") (pintype "passive"))
      (node (ref "J1") (pin "S2") (pinfunction "SHIELD_S2") (pintype "passive"))
    )
    (net (code "75") (name "Net-(J2-Pad10)") (class "Default")
      (node (ref "J2") (pin "10") (pinfunction "10_10") (pintype "passive"))
      (node (ref "R102") (pin "2") (pinfunction "2_2") (pintype "passive"))
    )
    (net (code "76") (name "Net-(J2-Pad12)") (class "Default")
      (node (ref "J2") (pin "12") (pinfunction "12_12") (pintype "passive"))
      (node (ref "R103") (pin "2") (pinfunction "2_2") (pintype "passive"))
    )
    (net (code "77") (name "Net-(J2-SHIELD-PadS1)") (class "Default")
      (node (ref "J2") (pin "S1") (pinfunction "SHIELD_S1") (pintype "passive"))
      (node (ref "J2") (pin "S2") (pinfunction "SHIELD_S2") (pintype "passive"))
    )
    (net (code "78") (name "Net-(Q_LEDA-D)") (class "Default")
      (node (ref "Q_LEDA") (pin "3") (pinfunction "D_3") (pintype "passive"))
      (node (ref "Q_LEDB") (pin "1") (pinfunction "G_1") (pintype "passive"))
      (node (ref "R_LEDB_O") (pin "1") (pinfunction "1_1") (pintype "passive"))
    )
    (net (code "79") (name "Net-(Q_LEDB-D)") (class "Default")
      (node (ref "Q_LEDB") (pin "3") (pinfunction "D_3") (pintype "passive"))
      (node (ref "R_LEDA_O") (pin "1") (pinfunction "1_1") (pintype "passive"))
    )
    (net (code "80") (name "Net-(R_1A_a-Pad2)") (class "Default")
      (node (ref "R_1A_a") (pin "2") (pinfunction "2_2") (pintype "passive"))
      (node (ref "R_1A_b") (pin "1") (pinfunction "1_1") (pintype "passive"))
    )
    (net (code "81") (name "Net-(R_1B_a-Pad2)") (class "Default")
      (node (ref "R_1B_a") (pin "2") (pinfunction "2_2") (pintype "passive"))
      (node (ref "R_1B_b") (pin "1") (pinfunction "1_1") (pintype "passive"))
    )
    (net (code "82") (name "PGND") (class "Default")
      (node (ref "D12") (pin "2") (pinfunction "A_2") (pintype "passive"))
      (node (ref "D9") (pin "2") (pinfunction "A_2") (pintype "passive"))
      (node (ref "Q3") (pin "3") (pinfunction "S_3") (pintype "passive"))
      (node (ref "Q4") (pin "3") (pinfunction "S_3") (pintype "passive"))
      (node (ref "R22") (pin "1") (pinfunction "1_1") (pintype "passive"))
      (node (ref "R23") (pin "2") (pinfunction "2_2") (pintype "passive"))
      (node (ref "R40") (pin "1") (pinfunction "1_1") (pintype "passive"))
      (node (ref "Rcsp") (pin "2") (pinfunction "2_2") (pintype "passive"))
    )
    (net (code "83") (name "VIN_N") (class "Default")
      (node (ref "C10") (pin "2") (pinfunction "2_2") (pintype "passive"))
      (node (ref "C11") (pin "2") (pinfunction "2_2") (pintype "passive"))
      (node (ref "C12") (pin "2") (pinfunction "2_2") (pintype "passive"))
      (node (ref "C130") (pin "2") (pinfunction "2_2") (pintype "passive"))
      (node (ref "C4") (pin "2") (pinfunction "2_2") (pintype "passive"))
      (node (ref "C5") (pin "2") (pinfunction "2_2") (pintype "passive"))
      (node (ref "C6") (pin "2") (pinfunction "2_2") (pintype "passive"))
      (node (ref "C7") (pin "2") (pinfunction "2_2") (pintype "passive"))
      (node (ref "C70") (pin "2") (pinfunction "2_2") (pintype "passive"))
      (node (ref "C72") (pin "2") (pinfunction "2_2") (pintype "passive"))
      (node (ref "C8") (pin "2") (pinfunction "2_2") (pintype "passive"))
      (node (ref "C9") (pin "2") (pinfunction "2_2") (pintype "passive"))
      (node (ref "D13") (pin "1") (pinfunction "K_1") (pintype "passive"))
      (node (ref "Q1") (pin "2") (pinfunction "D_2") (pintype "passive"))
      (node (ref "R1") (pin "1") (pinfunction "1_1") (pintype "passive"))
      (node (ref "Riinsns2") (pin "2") (pinfunction "2_2") (pintype "passive"))
      (node (ref "Rvisns") (pin "1") (pinfunction "1_1") (pintype "passive"))
    )
    (net (code "84") (name "VIN_P") (class "Default")
      (node (ref "C41") (pin "2") (pinfunction "2_2") (pintype "passive"))
      (node (ref "C45") (pin "2") (pinfunction "2_2") (pintype "passive"))
      (node (ref "C52") (pin "2") (pinfunction "2_2") (pintype "passive"))
      (node (ref "C620") (pin "2") (pinfunction "2_2") (pintype "passive"))
      (node (ref "D1_a") (pin "1") (pinfunction "K_1") (pintype "passive"))
      (node (ref "D1_b") (pin "1") (pinfunction "K_1") (pintype "passive"))
      (node (ref "D1_c") (pin "1") (pinfunction "K_1") (pintype "passive"))
      (node (ref "D1_d") (pin "1") (pinfunction "K_1") (pintype "passive"))
      (node (ref "D1_e") (pin "1") (pinfunction "K_1") (pintype "passive"))
      (node (ref "D1_f") (pin "1") (pinfunction "K_1") (pintype "passive"))
      (node (ref "D2_a") (pin "1") (pinfunction "K_1") (pintype "passive"))
      (node (ref "D2_b") (pin "1") (pinfunction "K_1") (pintype "passive"))
      (node (ref "D2_c") (pin "1") (pinfunction "K_1") (pintype "passive"))
      (node (ref "D2_d") (pin "1") (pinfunction "K_1") (pintype "passive"))
      (node (ref "D2_e") (pin "1") (pinfunction "K_1") (pintype "passive"))
      (node (ref "D2_f") (pin "1") (pinfunction "K_1") (pintype "passive"))
      (node (ref "D_CLAMP_1") (pin "1") (pinfunction "K_1") (pintype "passive"))
      (node (ref "Df") (pin "2") (pinfunction "A_2") (pintype "passive"))
      (node (ref "R1") (pin "2") (pinfunction "2_2") (pintype "passive"))
      (node (ref "R53") (pin "2") (pinfunction "2_2") (pintype "passive"))
      (node (ref "Riinsns1") (pin "2") (pinfunction "2_2") (pintype "passive"))
      (node (ref "Ruvt") (pin "2") (pinfunction "2_2") (pintype "passive"))
    )
    (net (code "85") (name "VOUT_N") (class "Default")
      (node (ref "C50") (pin "2") (pinfunction "2_2") (pintype "passive"))
      (node (ref "C51") (pin "2") (pinfunction "2_2") (pintype "passive"))
      (node (ref "C54") (pin "2") (pinfunction "2_2") (pintype "passive"))
      (node (ref "C55") (pin "2") (pinfunction "2_2") (pintype "passive"))
      (node (ref "R10") (pin "2") (pinfunction "2_2") (pintype "passive"))
      (node (ref "R13") (pin "2") (pinfunction "2_2") (pintype "passive"))
      (node (ref "Rioutsns2") (pin "2") (pinfunction "2_2") (pintype "passive"))
      (node (ref "U1") (pin "12") (pinfunction "VOSNS_12") (pintype "input"))
    )
    (net (code "86") (name "VOUT_P") (class "Default")
      (node (ref "C1") (pin "2") (pinfunction "2_2") (pintype "passive"))
      (node (ref "C16") (pin "2") (pinfunction "2_2") (pintype "passive"))
      (node (ref "C20") (pin "2") (pinfunction "2_2") (pintype "passive"))
      (node (ref "C25") (pin "2") (pinfunction "2_2") (pintype "passive"))
      (node (ref "C27") (pin "2") (pinfunction "2_2") (pintype "passive"))
      (node (ref "C28") (pin "2") (pinfunction "2_2") (pintype "passive"))
      (node (ref "C30") (pin "2") (pinfunction "2_2") (pintype "passive"))
      (node (ref "C36") (pin "2") (pinfunction "2_2") (pintype "passive"))
      (node (ref "C410") (pin "2") (pinfunction "2_2") (pintype "passive"))
      (node (ref "C44") (pin "2") (pinfunction "2_2") (pintype "passive"))
      (node (ref "C450") (pin "2") (pinfunction "2_2") (pintype "passive"))
      (node (ref "C470") (pin "2") (pinfunction "2_2") (pintype "passive"))
      (node (ref "D7") (pin "1") (pinfunction "K_1") (pintype "passive"))
      (node (ref "Q2") (pin "2") (pinfunction "D_2") (pintype "passive"))
      (node (ref "R10") (pin "1") (pinfunction "1_1") (pintype "passive"))
      (node (ref "Rioutsns1") (pin "2") (pinfunction "2_2") (pintype "passive"))
    )
  )
)
